# RFFI_pwrCtrl_Integrated_rev02_2021-05-18.net
KiCad netlist of a schematic drawn in EasyEDA
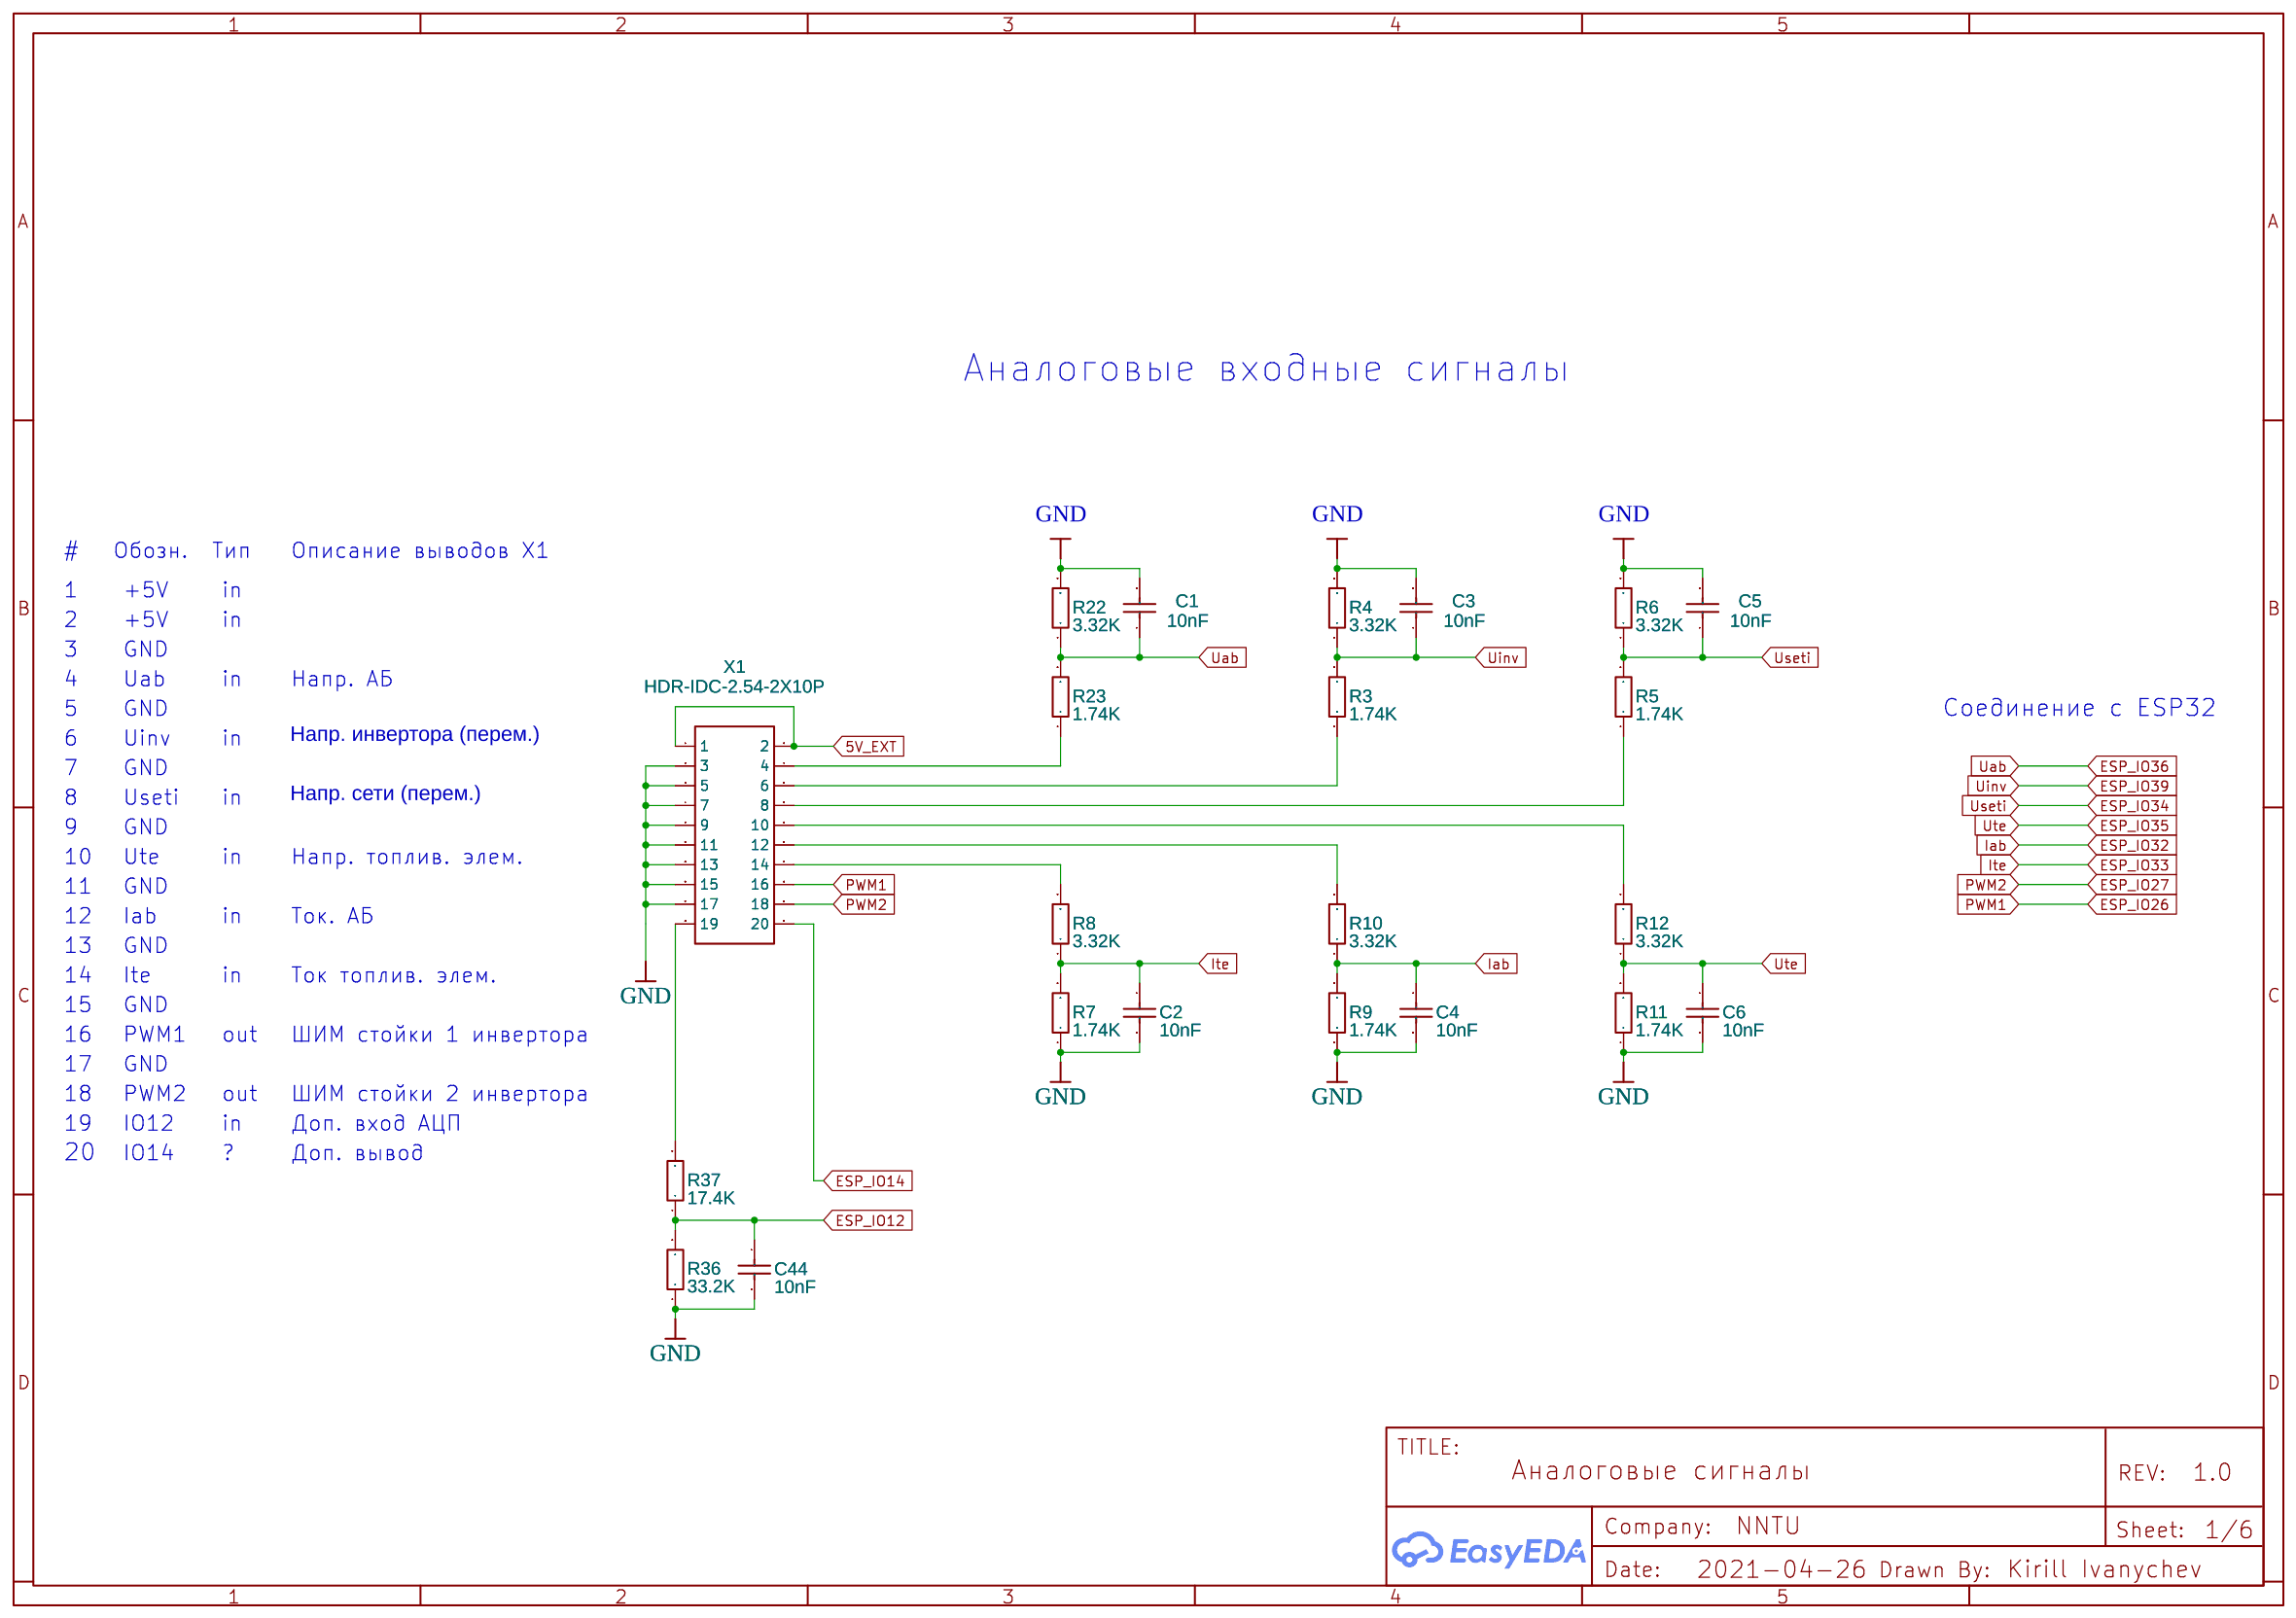
[diagram p0: Analog Signals]
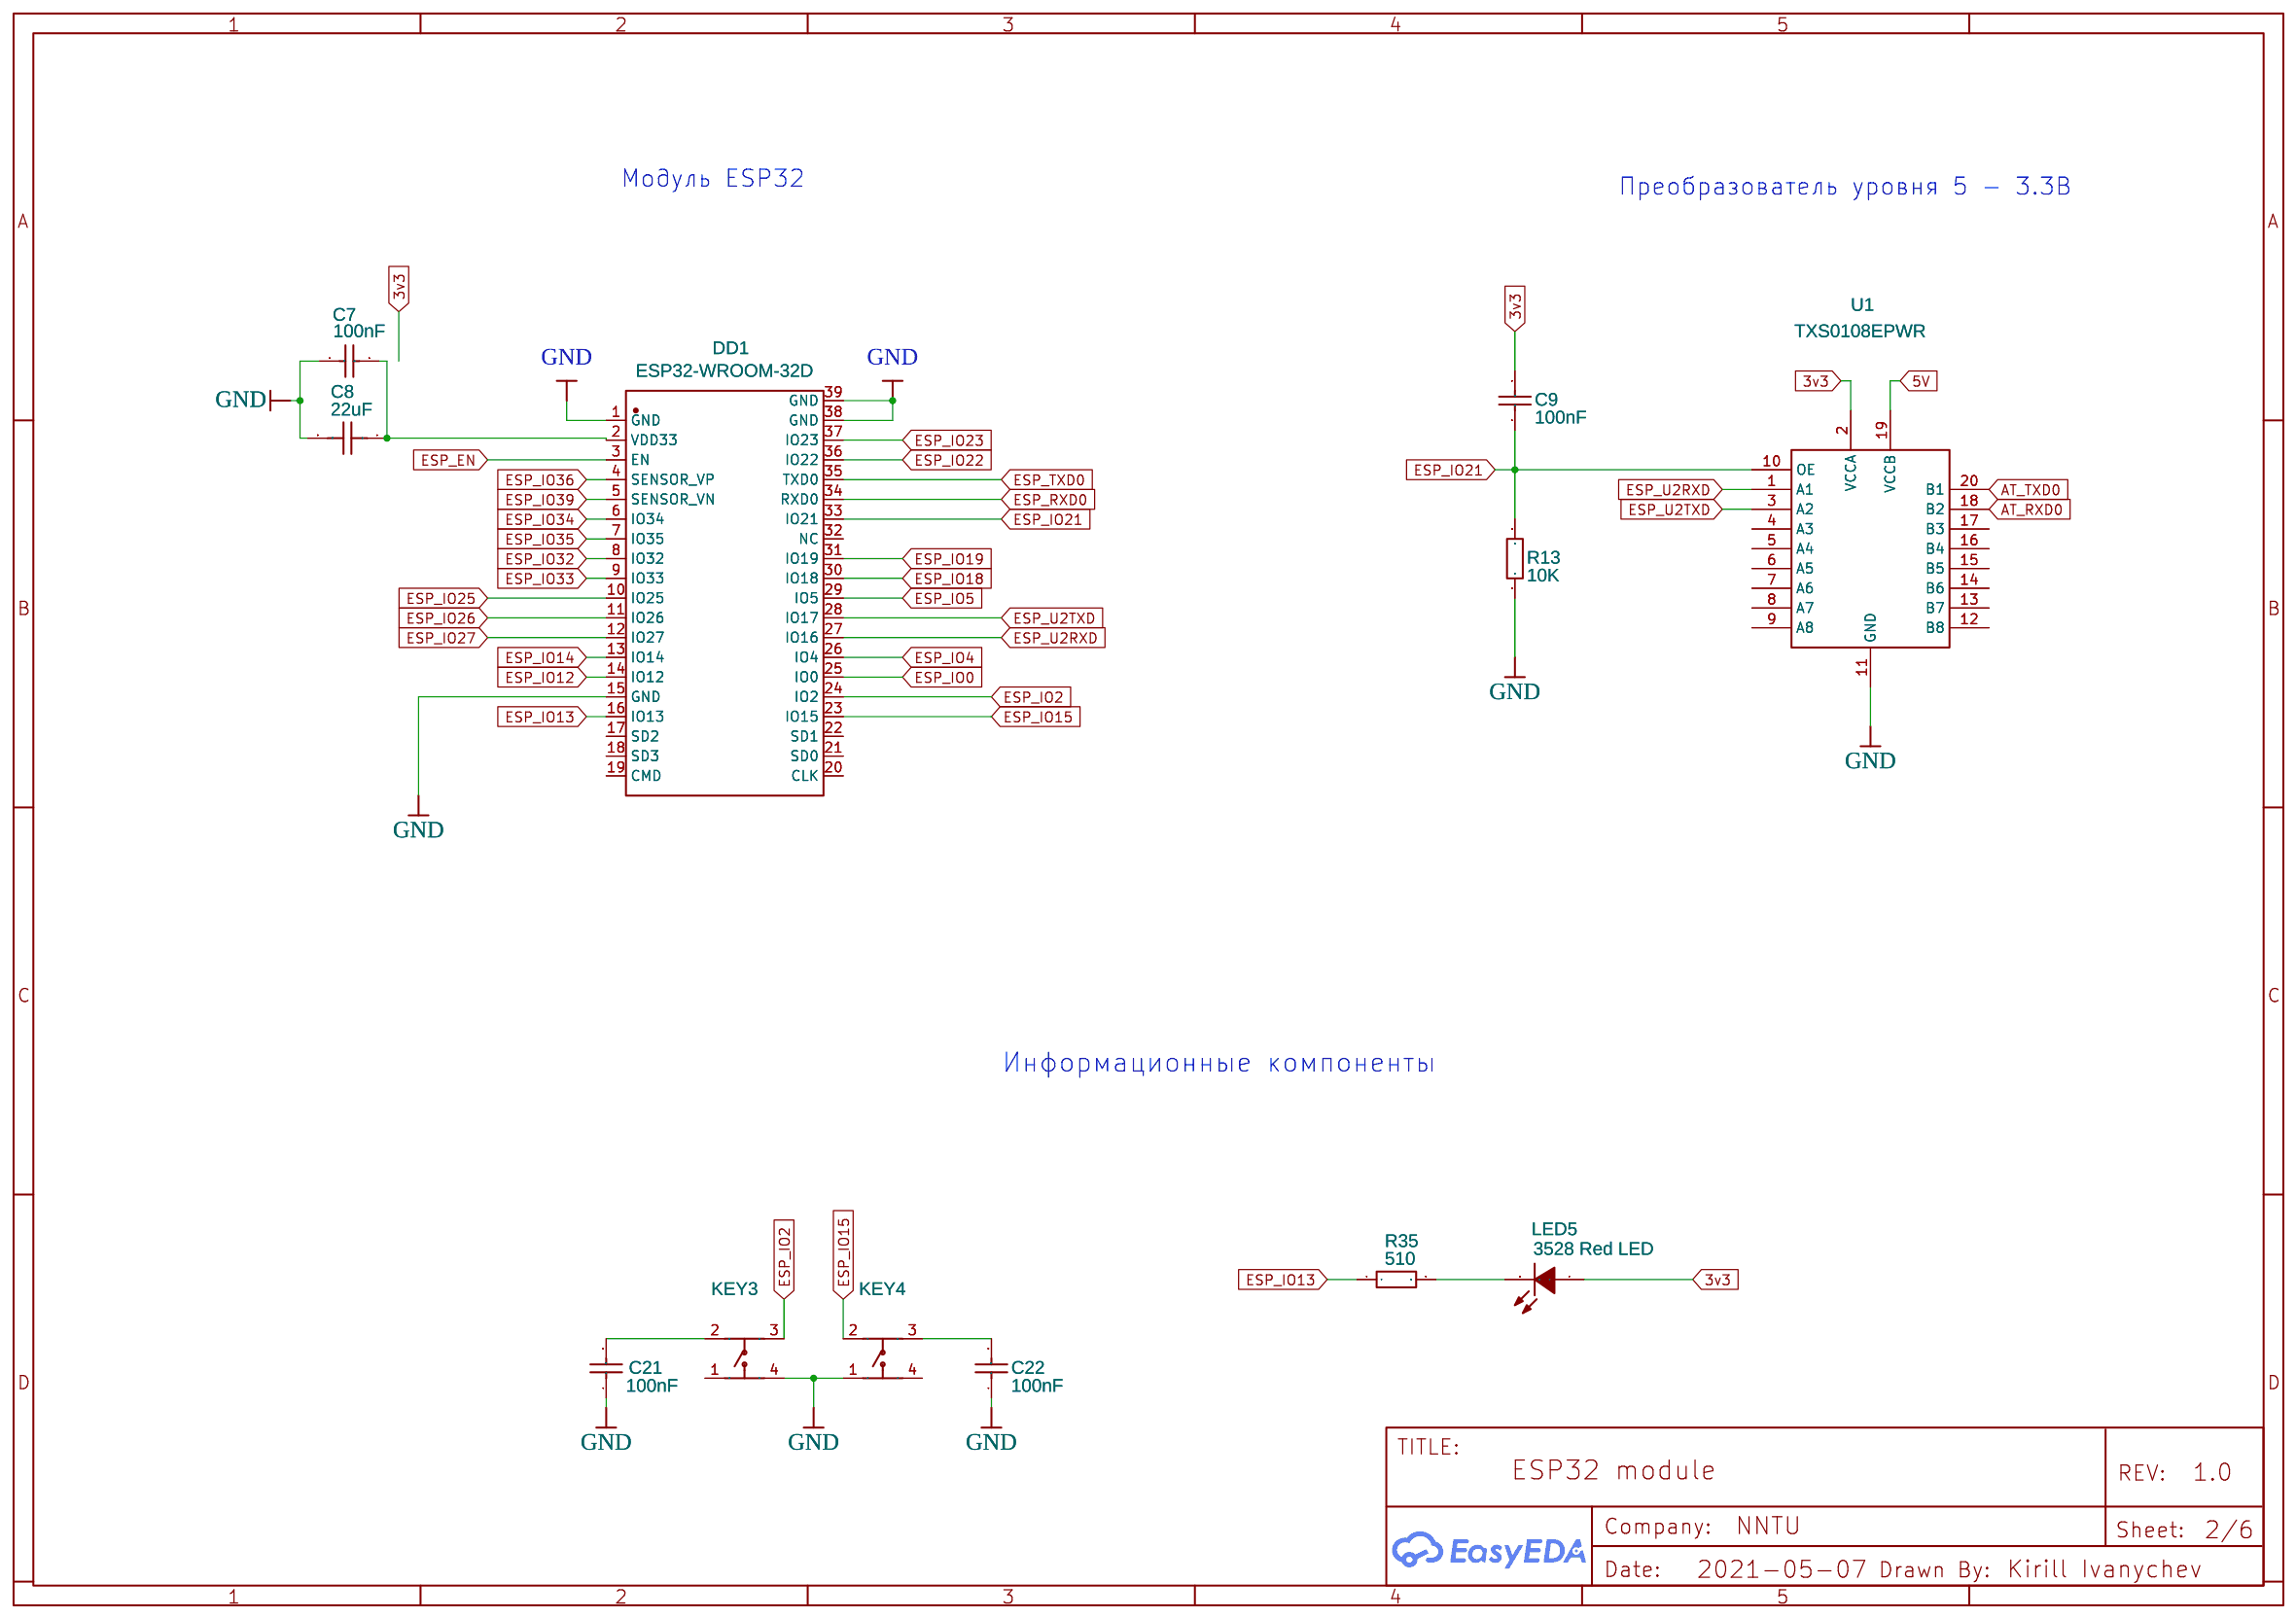
[diagram p1: ESP32 module]
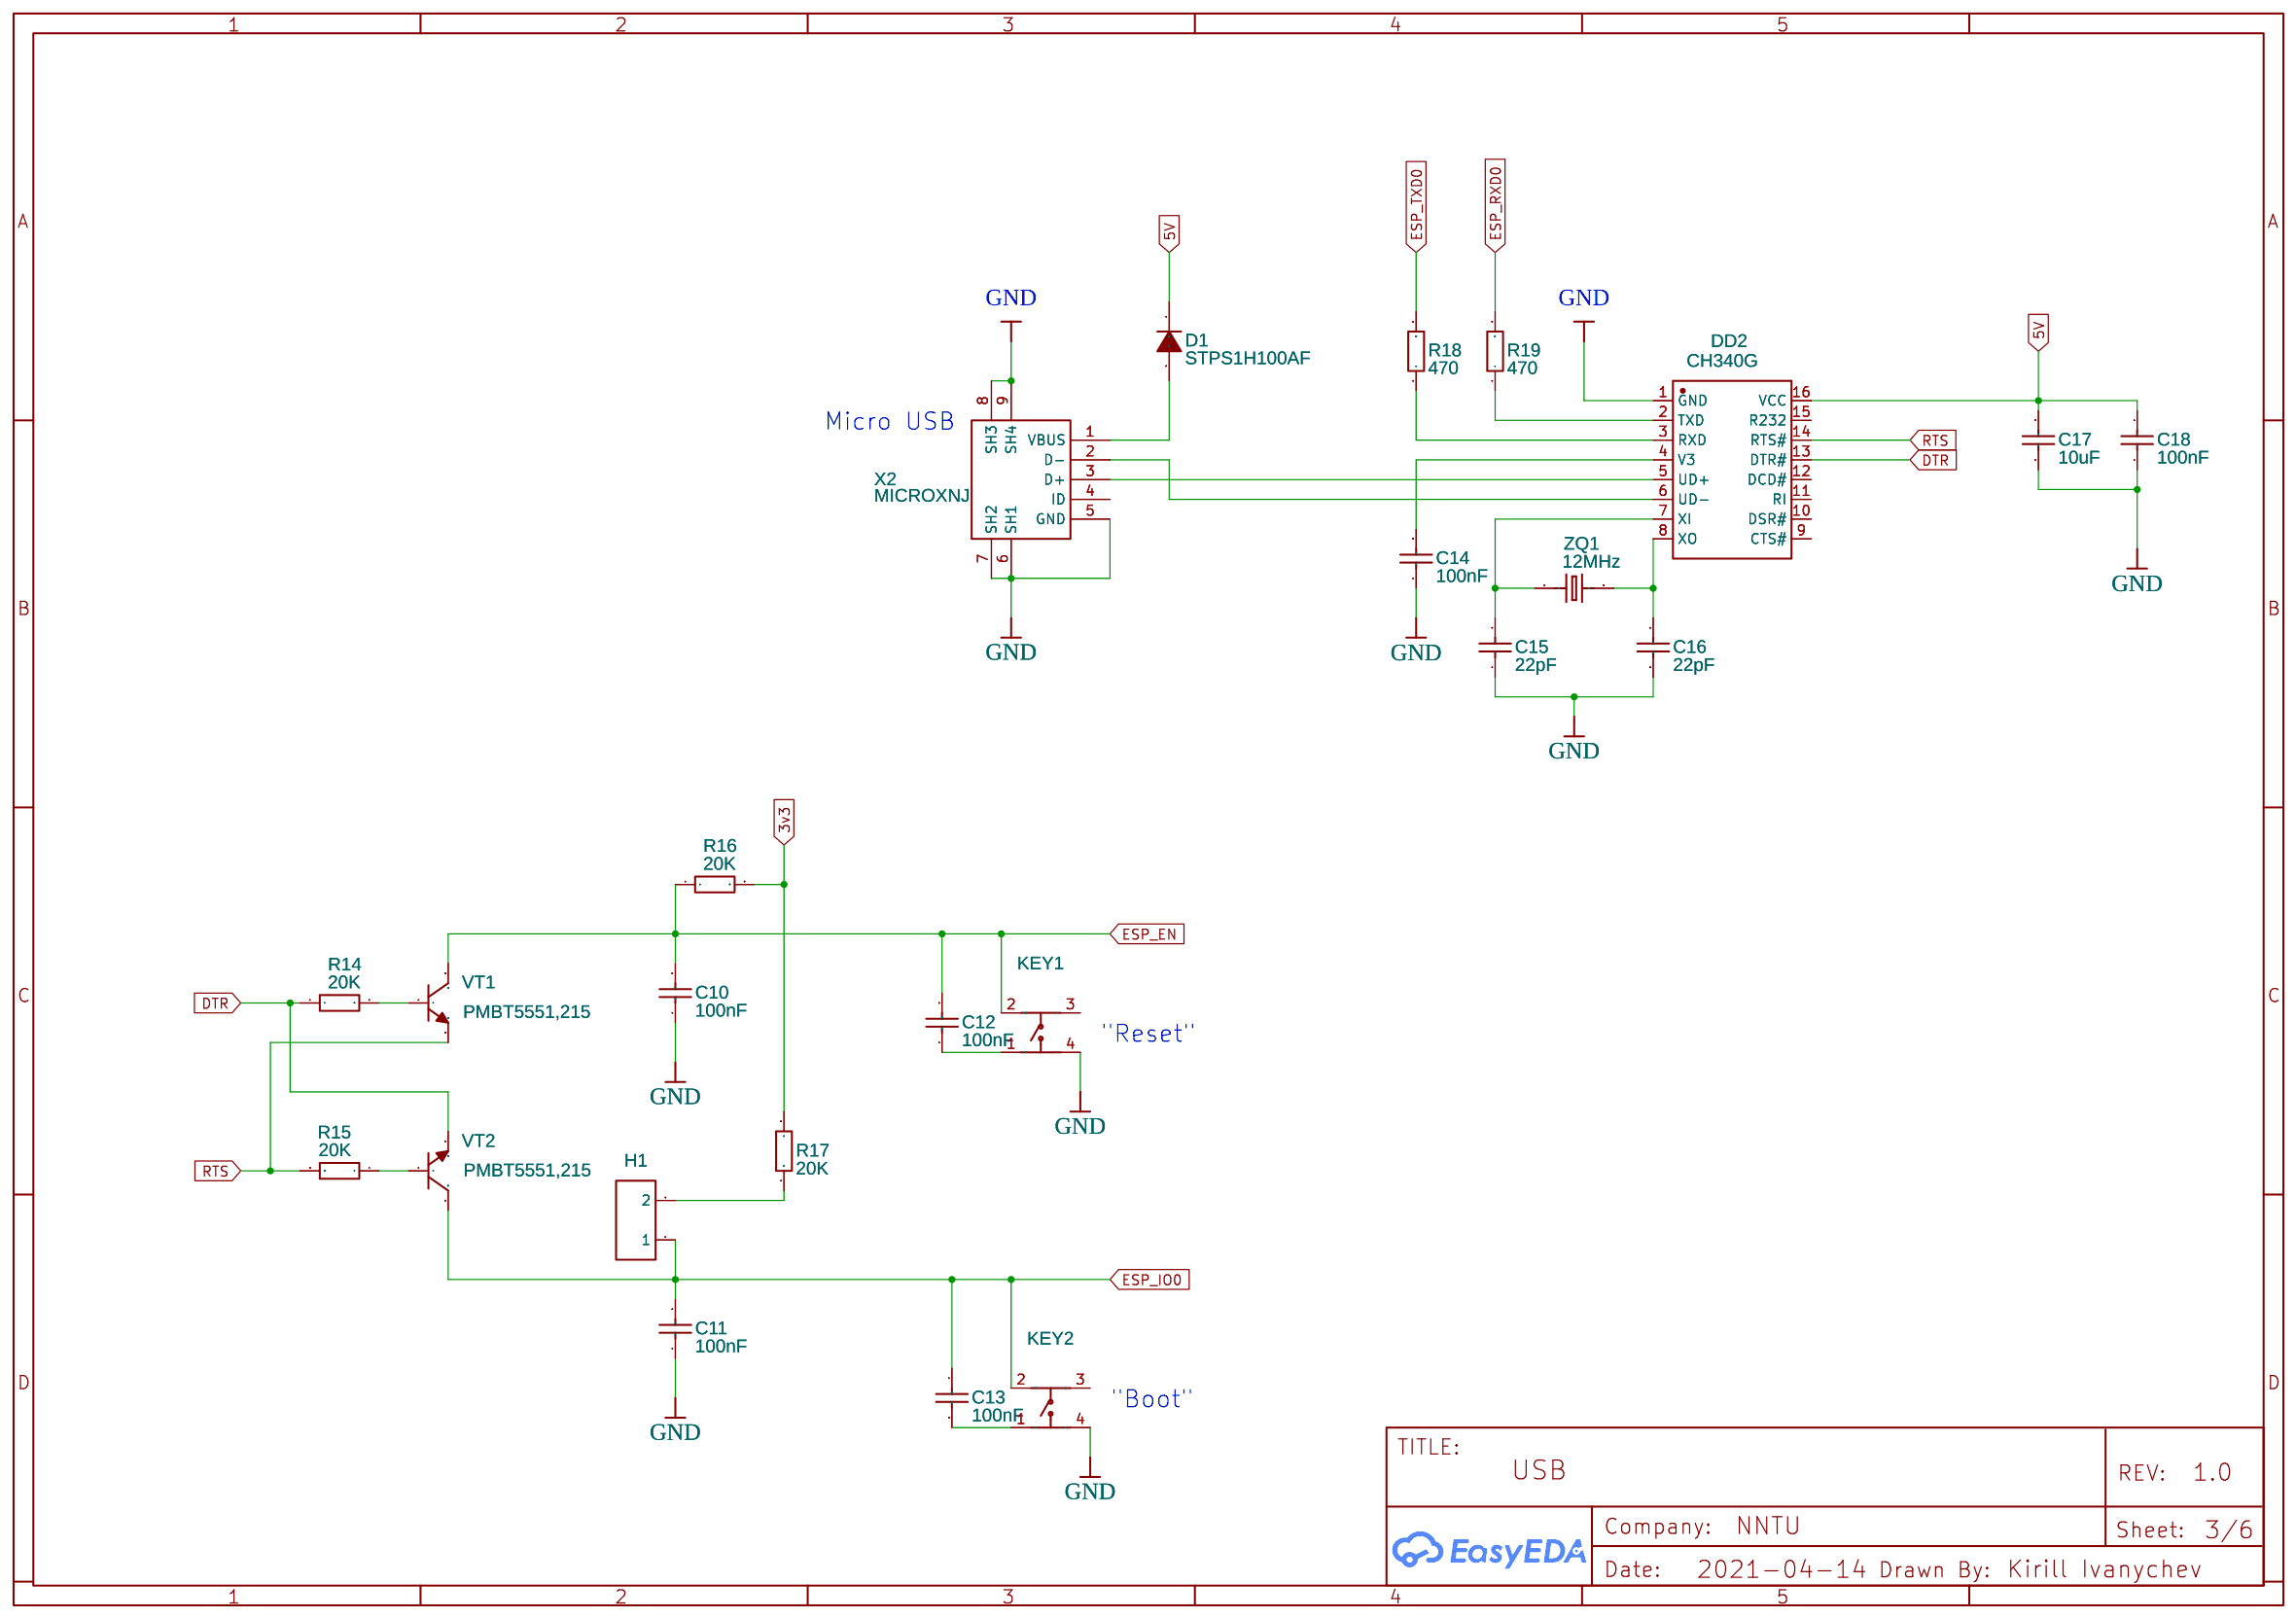
[diagram p2: USB]
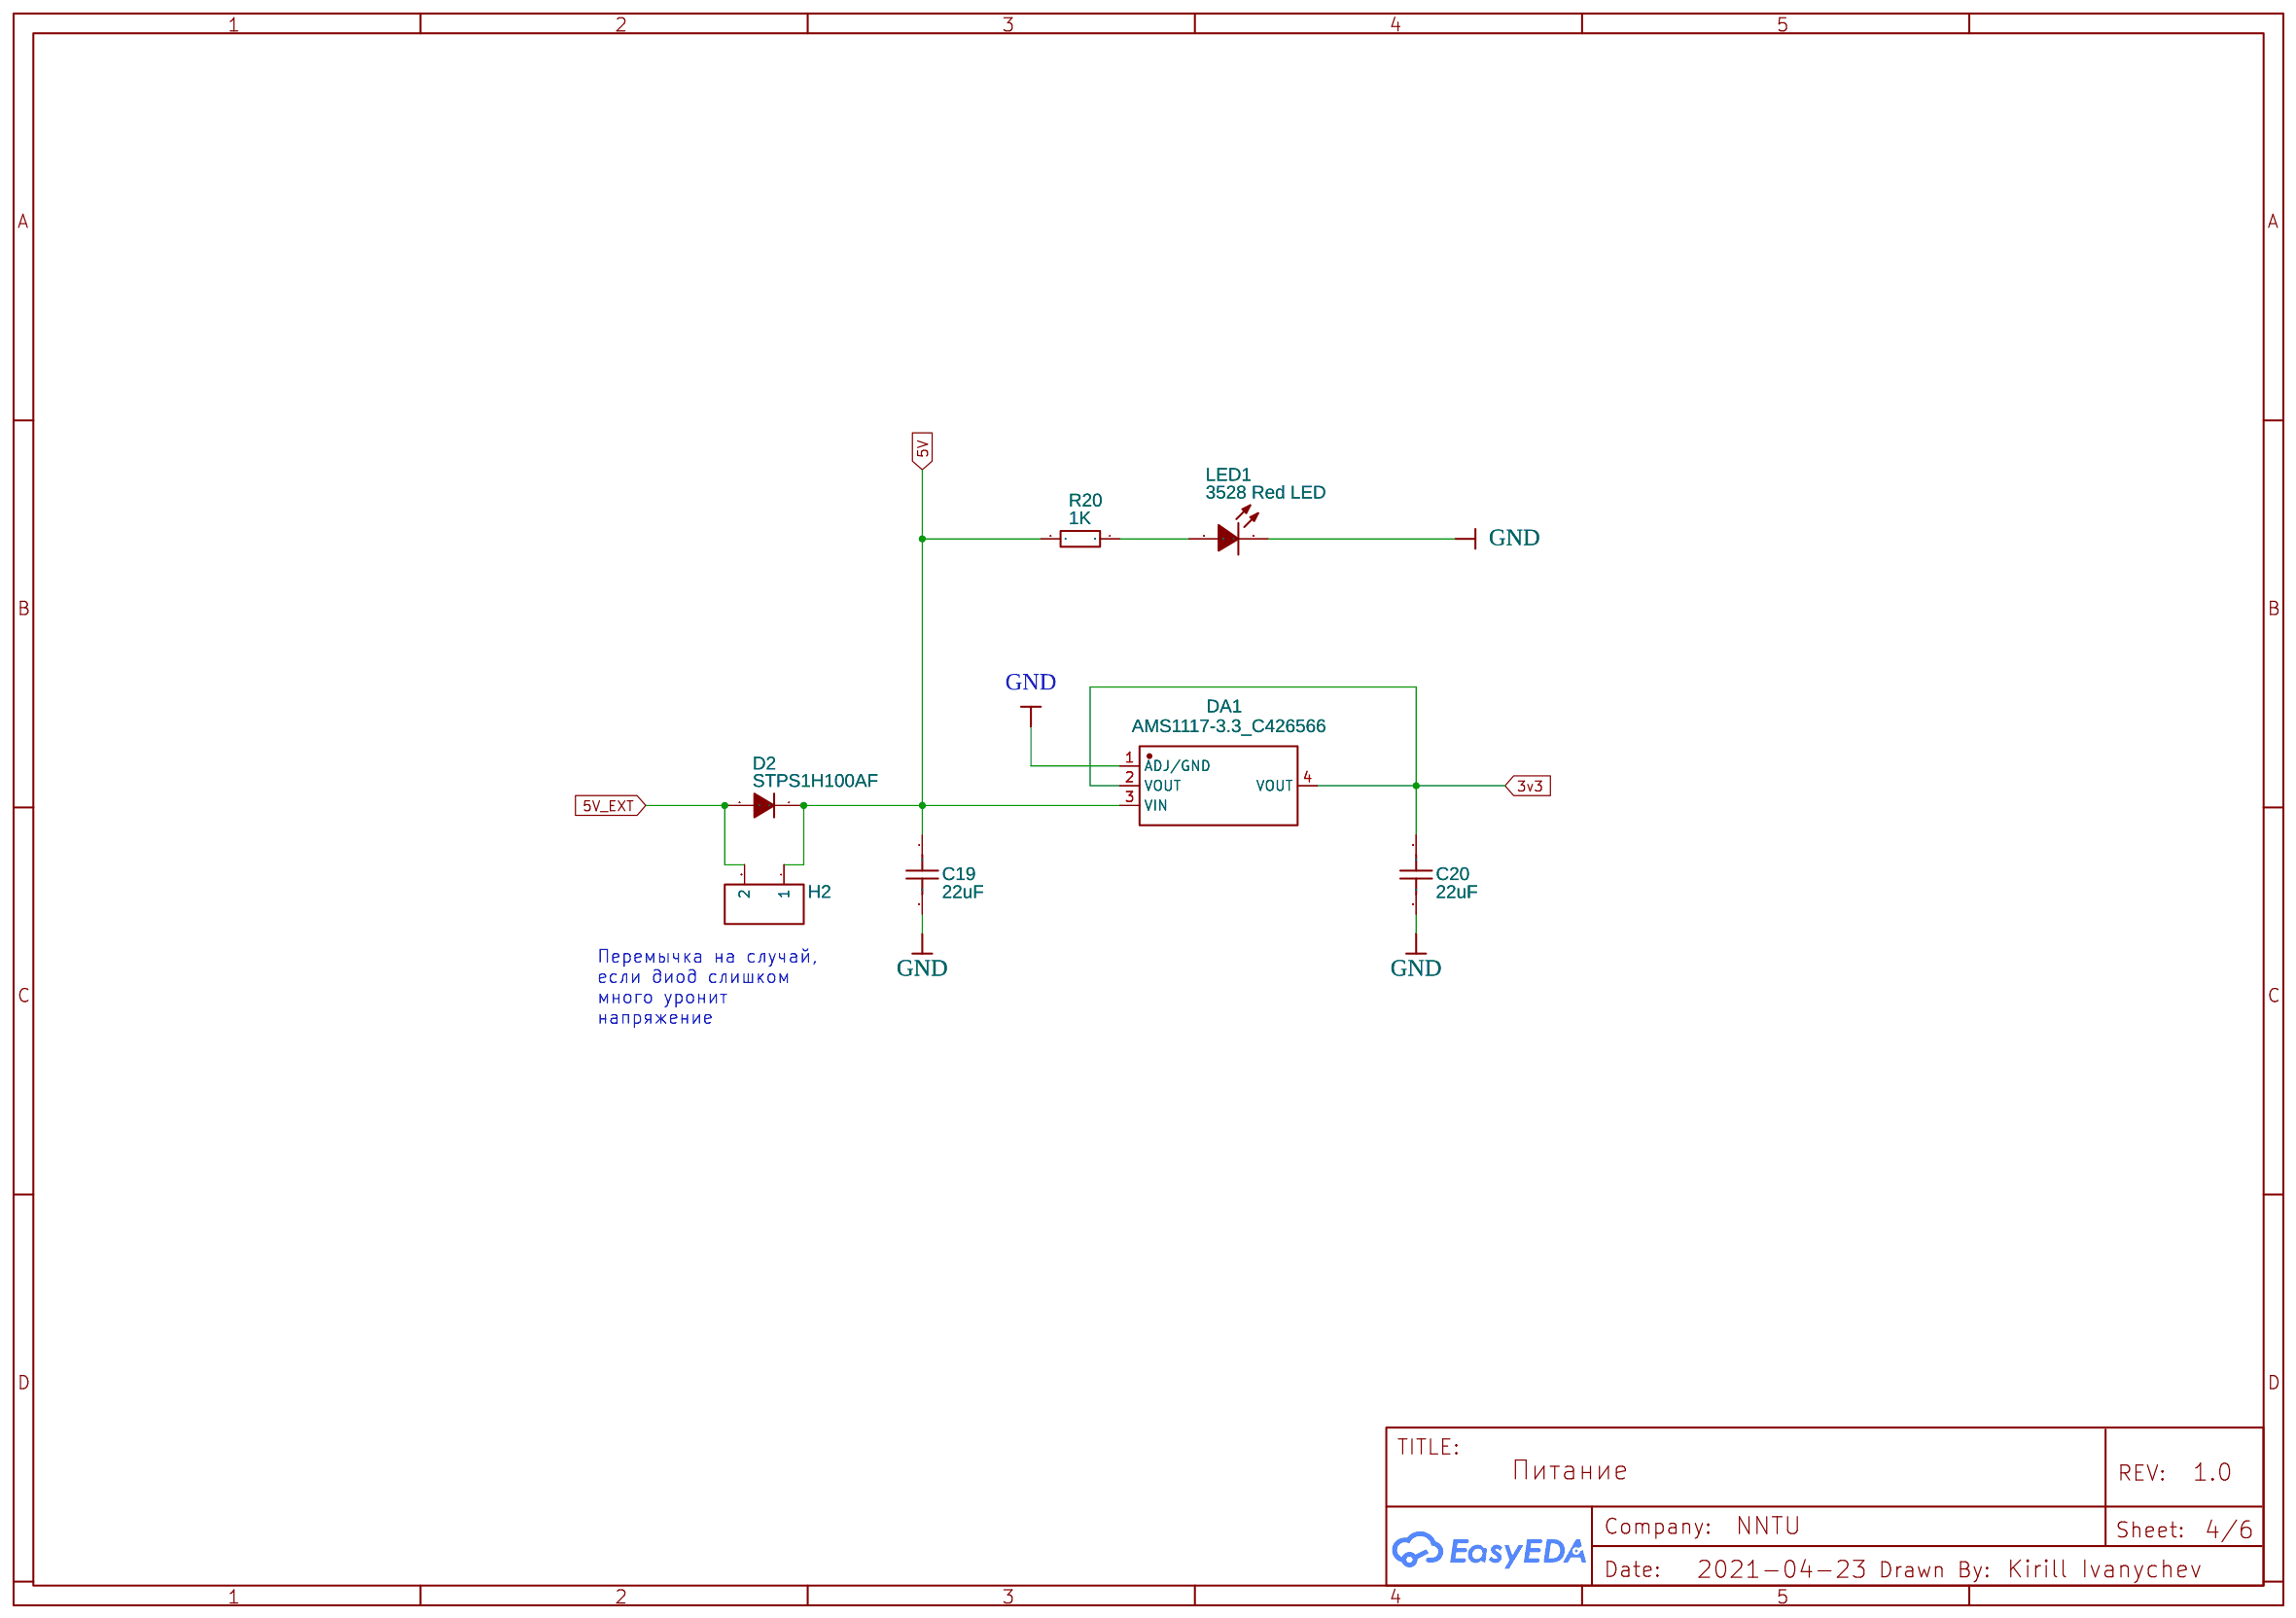
[diagram p3: Power]
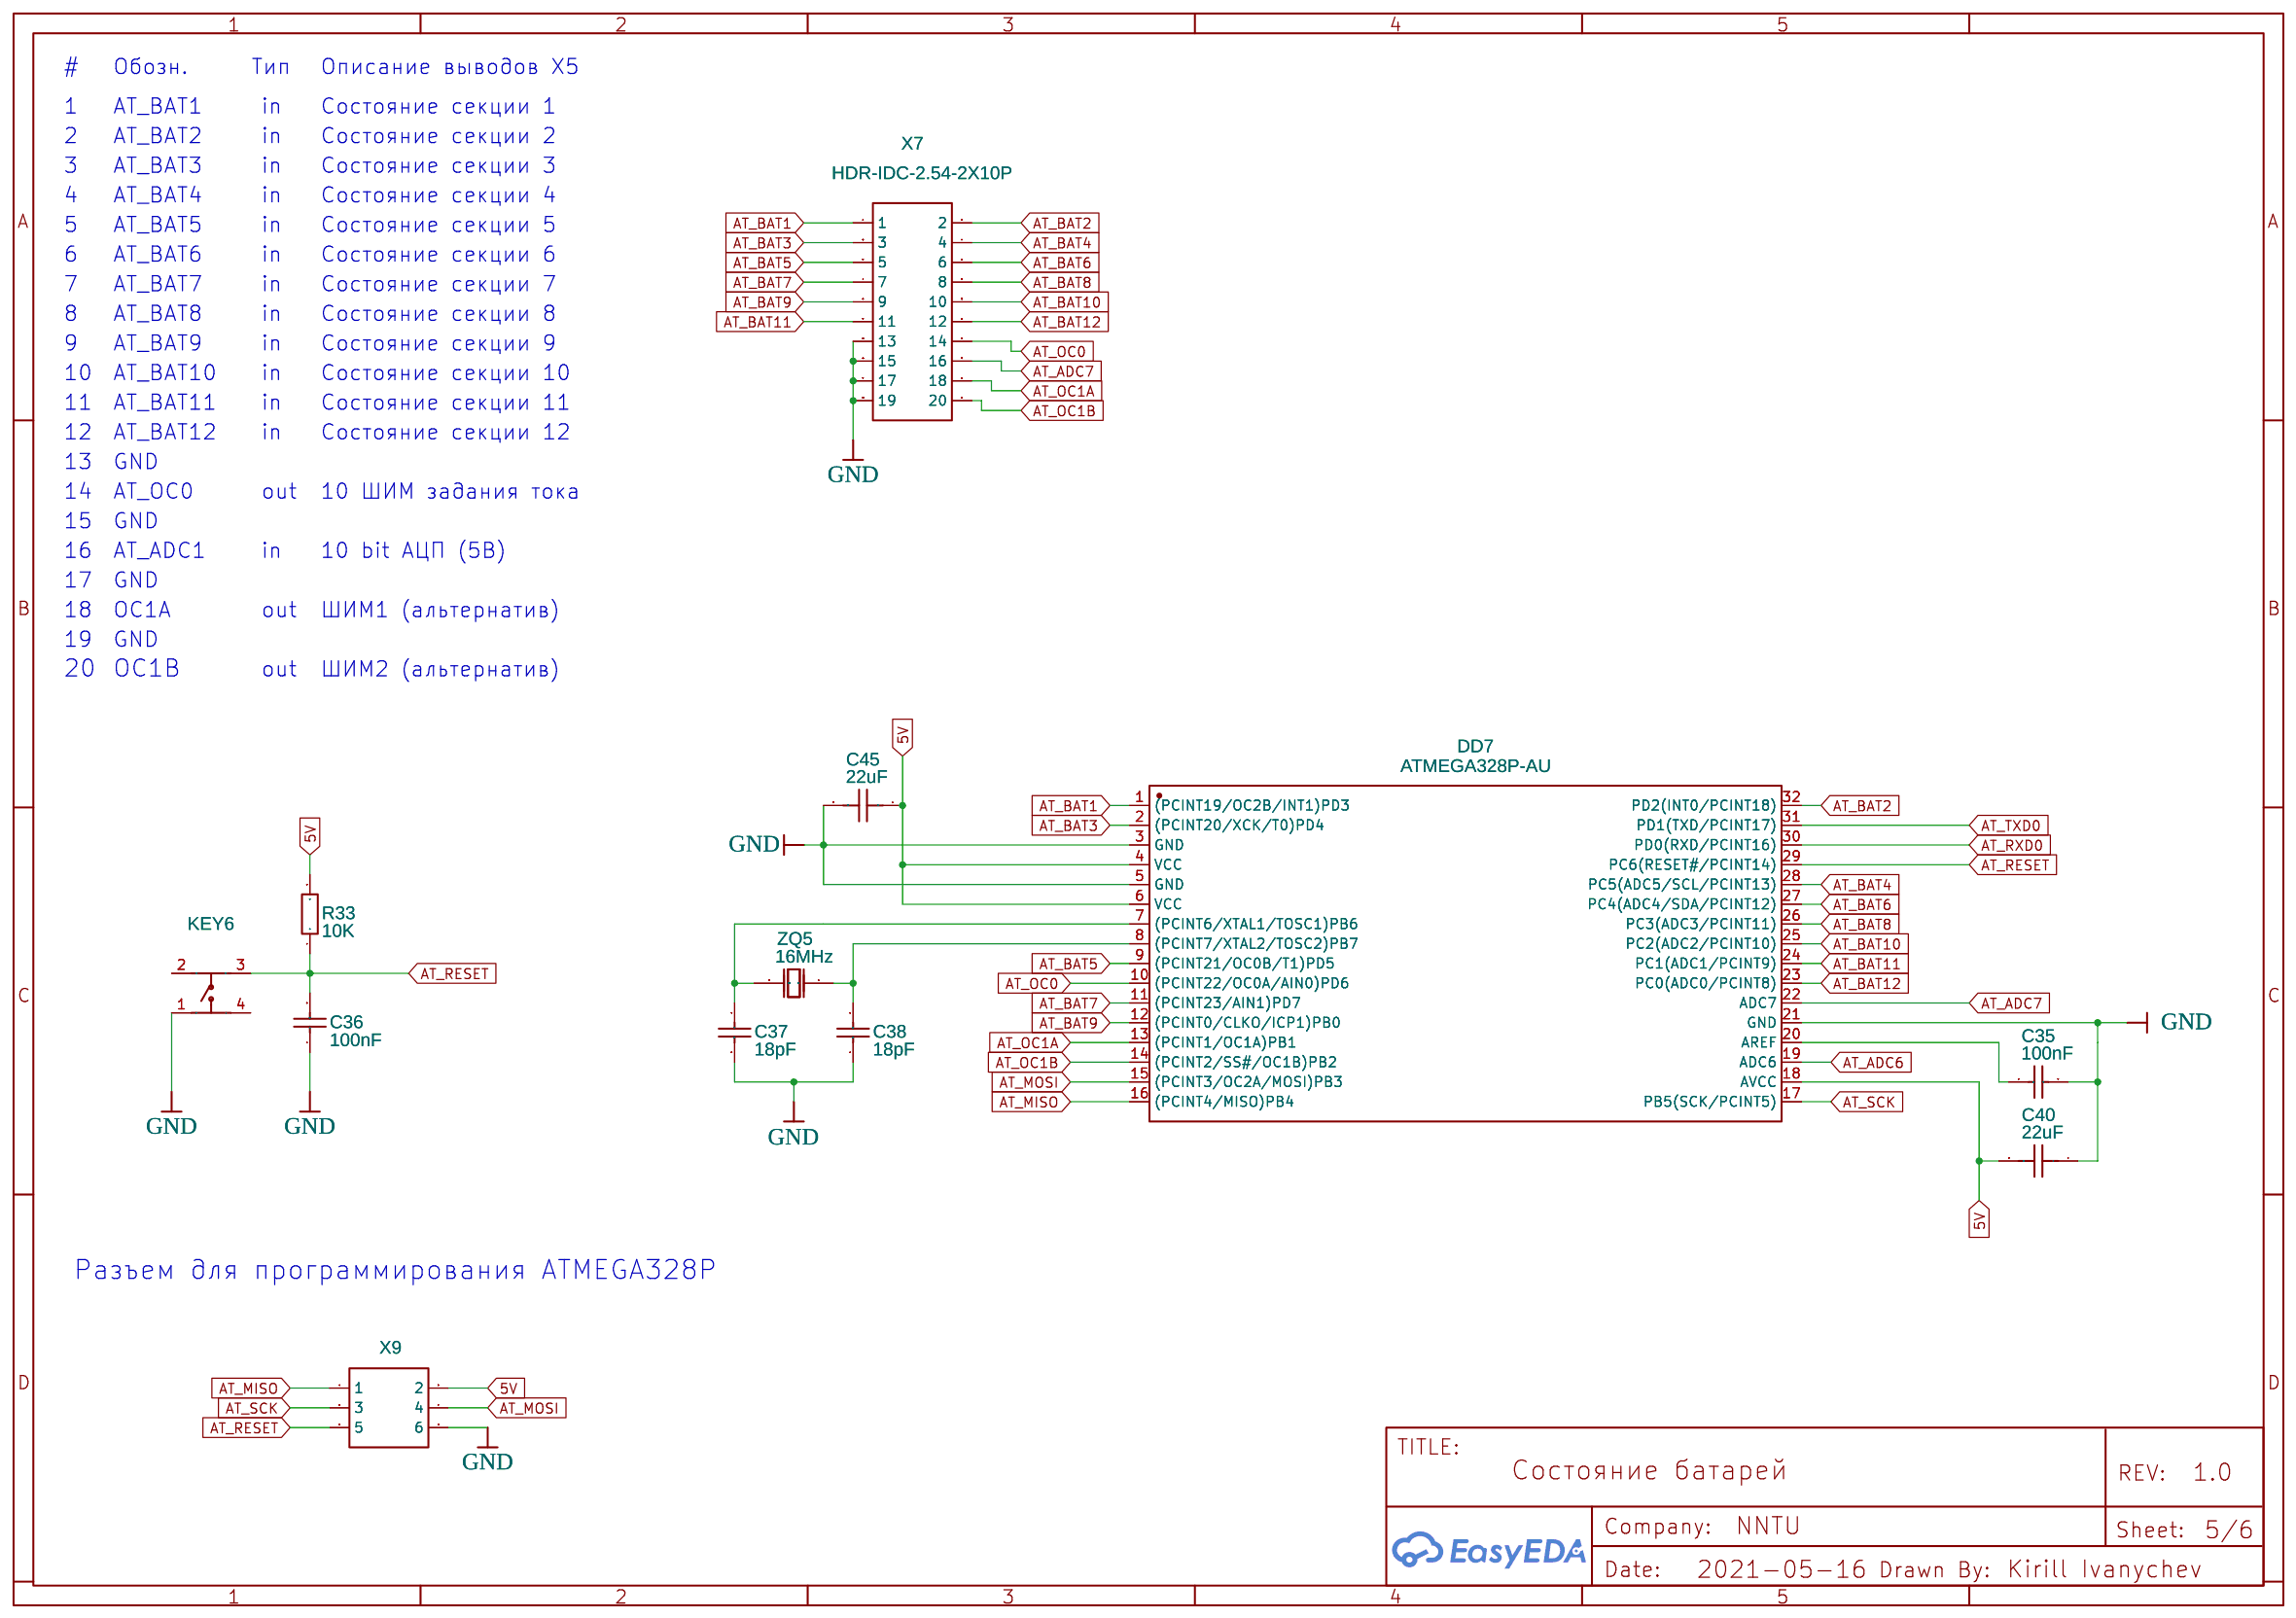
[diagram p4: Batteries]
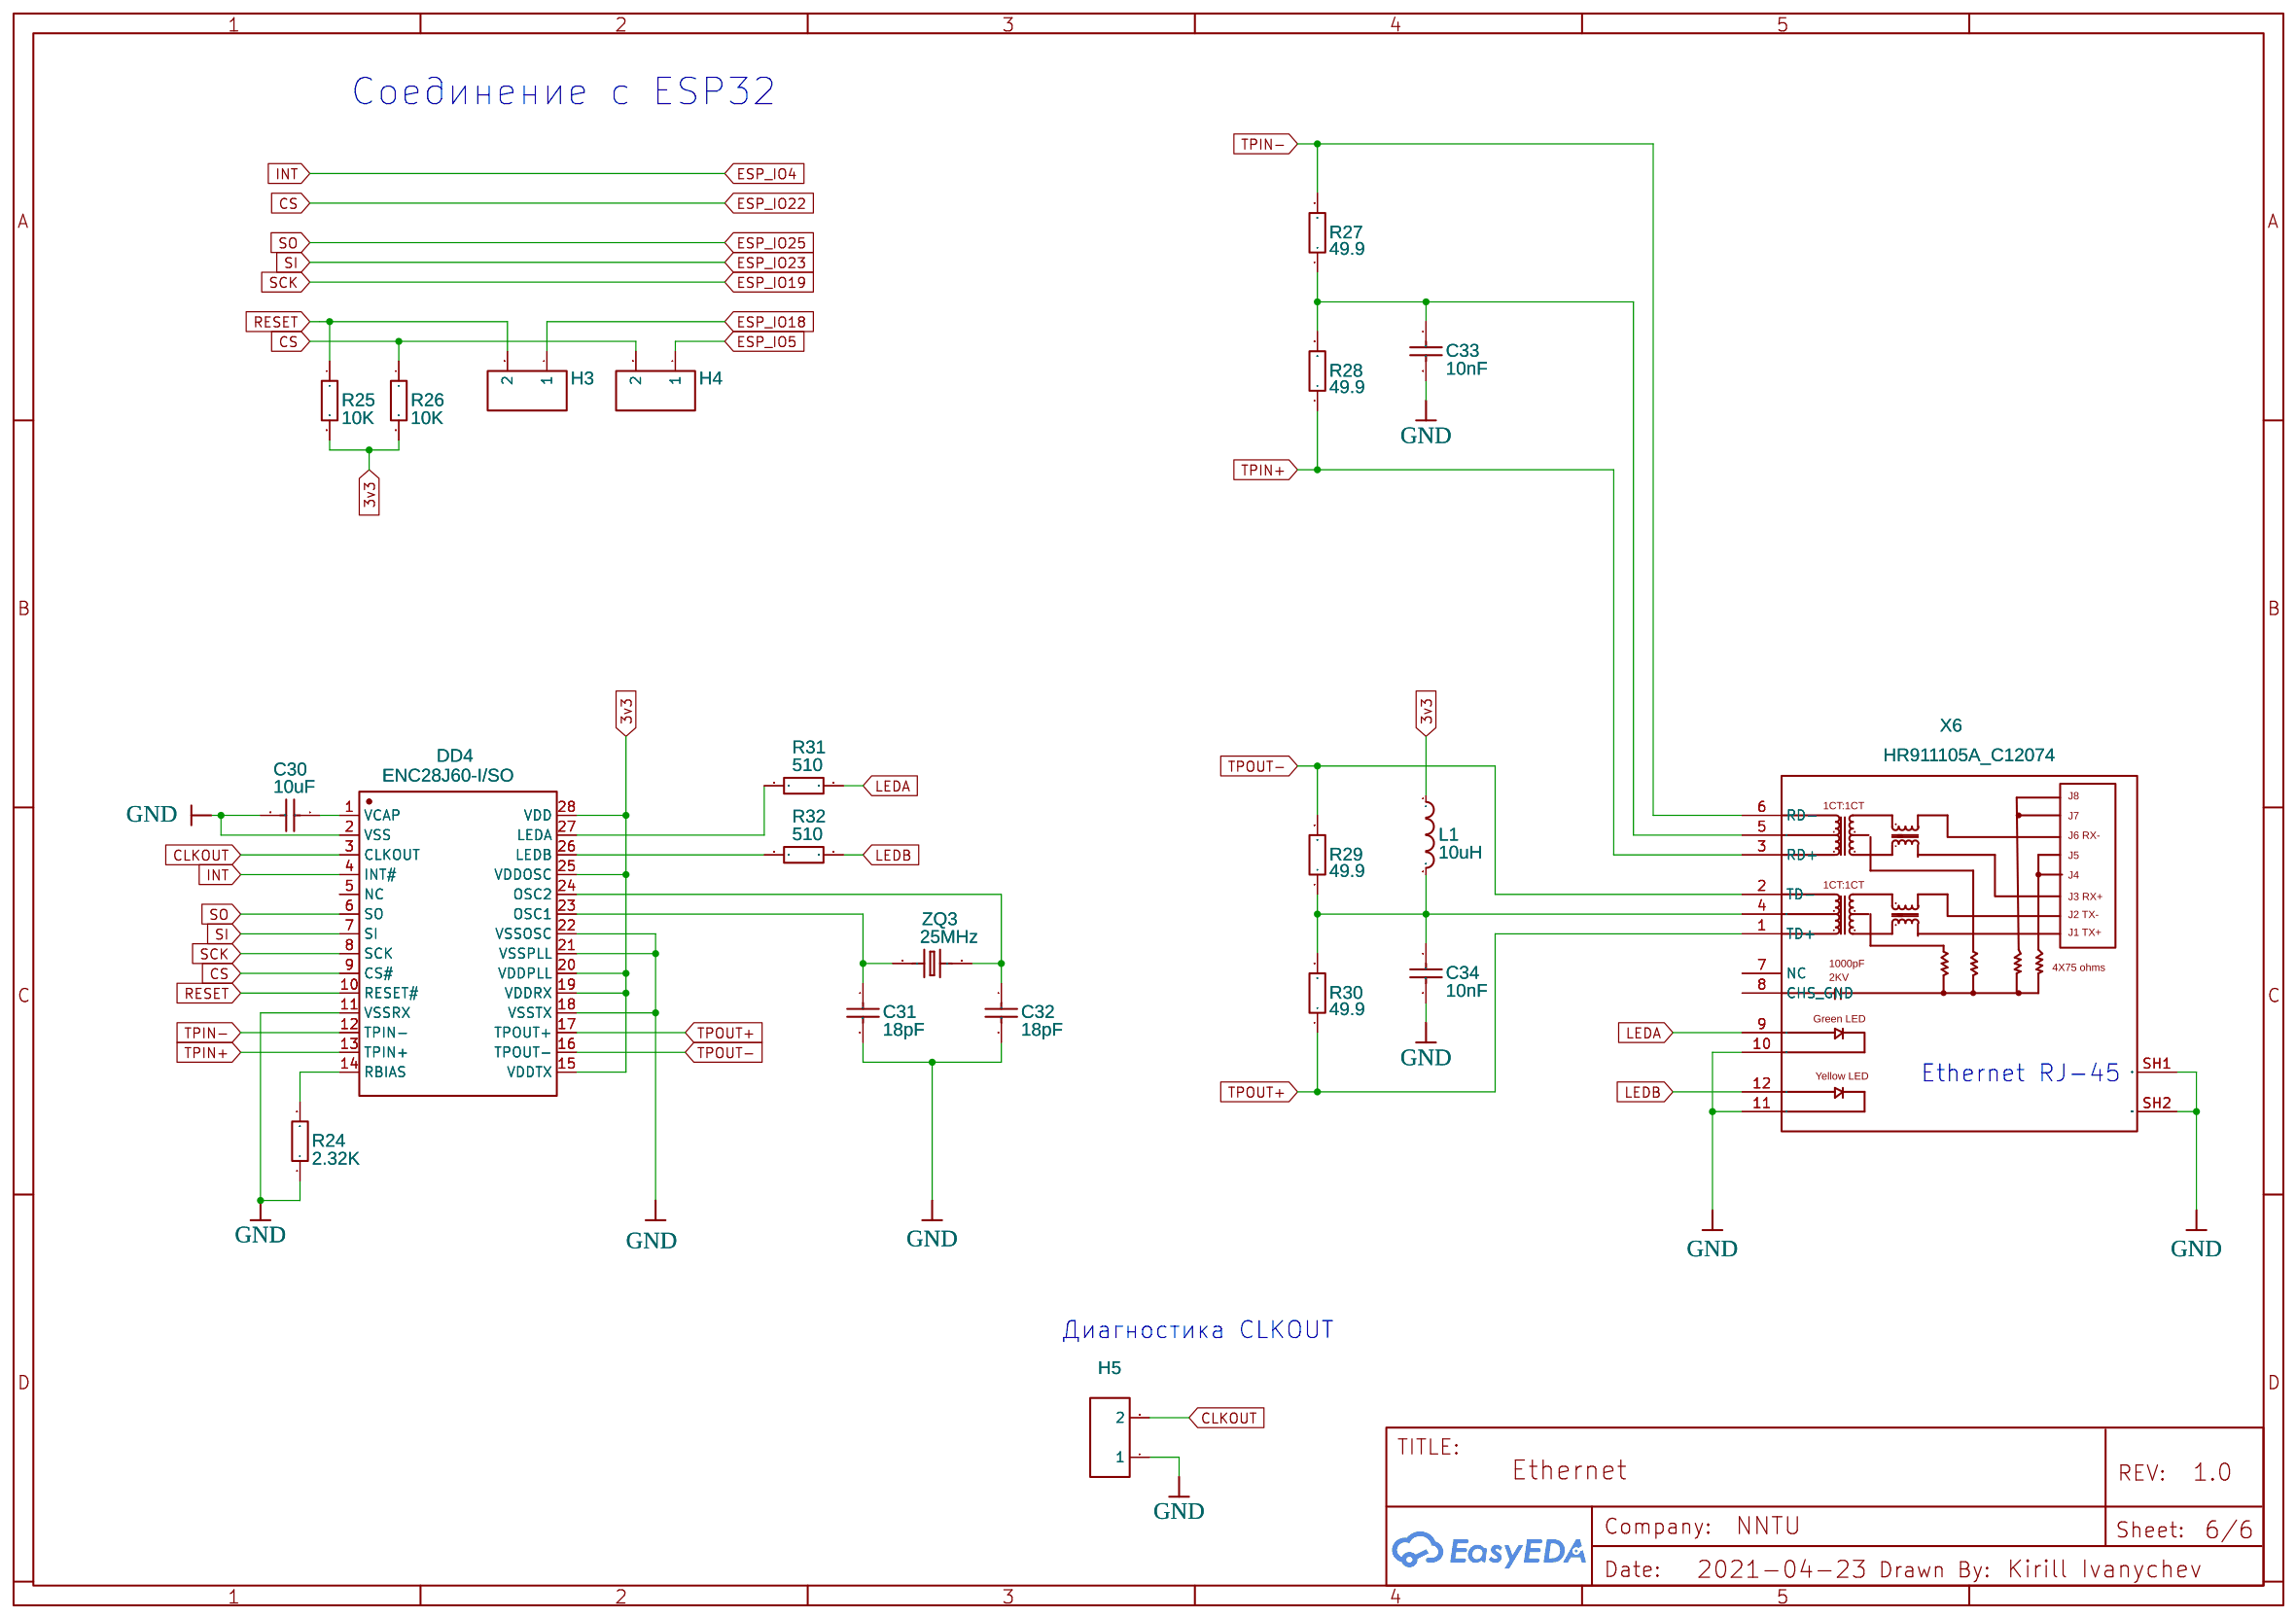
[diagram p5: Ethernet]

(export (version "E")
  (design (tool "Eeschema 10.0.6"))
  (components
    (comp (ref "C1")
      (value "10nF")
      (fields
        (field (name "BOM_Manufacturer Part") "1206B103K500NT")
        (field (name "BOM_Supplier Part") "C1846")
      )
      (libsource (lib "") (part "1206B103K500NT_1"))
    )
    (comp (ref "C2")
      (value "10nF")
      (fields
        (field (name "BOM_Manufacturer Part") "1206B103K500NT")
        (field (name "BOM_Supplier Part") "C1846")
      )
      (libsource (lib "") (part "1206B103K500NT"))
    )
    (comp (ref "C3")
      (value "10nF")
      (fields
        (field (name "BOM_Manufacturer Part") "1206B103K500NT")
        (field (name "BOM_Supplier Part") "C1846")
      )
      (libsource (lib "") (part "1206B103K500NT_1"))
    )
    (comp (ref "C4")
      (value "10nF")
      (fields
        (field (name "BOM_Manufacturer Part") "1206B103K500NT")
        (field (name "BOM_Supplier Part") "C1846")
      )
      (libsource (lib "") (part "1206B103K500NT"))
    )
    (comp (ref "C5")
      (value "10nF")
      (fields
        (field (name "BOM_Manufacturer Part") "1206B103K500NT")
        (field (name "BOM_Supplier Part") "C1846")
      )
      (libsource (lib "") (part "1206B103K500NT_1"))
    )
    (comp (ref "C6")
      (value "10nF")
      (fields
        (field (name "BOM_Manufacturer Part") "1206B103K500NT")
        (field (name "BOM_Supplier Part") "C1846")
      )
      (libsource (lib "") (part "1206B103K500NT"))
    )
    (comp (ref "C44")
      (value "10nF")
      (fields
        (field (name "BOM_Manufacturer Part") "1206B103K500NT")
        (field (name "BOM_Supplier Part") "C1846")
      )
      (libsource (lib "") (part "1206B103K500NT"))
    )
    (comp (ref "R3")
      (value "1.74K")
      (fields
        (field (name "BOM_Manufacturer Part") "0402WGF1741TCE")
        (field (name "BOM_Supplier Part") "C270638")
      )
      (libsource (lib "") (part "0402WGF1741TCE"))
    )
    (comp (ref "R4")
      (value "3.32K")
      (fields
        (field (name "BOM_Manufacturer Part") "0603WAF3321T5E")
        (field (name "BOM_Supplier Part") "C22995")
      )
      (libsource (lib "") (part "0603WAF3321T5E"))
    )
    (comp (ref "R5")
      (value "1.74K")
      (fields
        (field (name "BOM_Manufacturer Part") "0402WGF1741TCE")
        (field (name "BOM_Supplier Part") "C270638")
      )
      (libsource (lib "") (part "0402WGF1741TCE"))
    )
    (comp (ref "R6")
      (value "3.32K")
      (fields
        (field (name "BOM_Manufacturer Part") "0603WAF3321T5E")
        (field (name "BOM_Supplier Part") "C22995")
      )
      (libsource (lib "") (part "0603WAF3321T5E"))
    )
    (comp (ref "R7")
      (value "1.74K")
      (fields
        (field (name "BOM_Manufacturer Part") "0402WGF1741TCE")
        (field (name "BOM_Supplier Part") "C270638")
      )
      (libsource (lib "") (part "0402WGF1741TCE"))
    )
    (comp (ref "R8")
      (value "3.32K")
      (fields
        (field (name "BOM_Manufacturer Part") "0603WAF3321T5E")
        (field (name "BOM_Supplier Part") "C22995")
      )
      (libsource (lib "") (part "0603WAF3321T5E"))
    )
    (comp (ref "R9")
      (value "1.74K")
      (fields
        (field (name "BOM_Manufacturer Part") "0402WGF1741TCE")
        (field (name "BOM_Supplier Part") "C270638")
      )
      (libsource (lib "") (part "0402WGF1741TCE"))
    )
    (comp (ref "R10")
      (value "3.32K")
      (fields
        (field (name "BOM_Manufacturer Part") "0603WAF3321T5E")
        (field (name "BOM_Supplier Part") "C22995")
      )
      (libsource (lib "") (part "0603WAF3321T5E"))
    )
    (comp (ref "R11")
      (value "1.74K")
      (fields
        (field (name "BOM_Manufacturer Part") "0402WGF1741TCE")
        (field (name "BOM_Supplier Part") "C270638")
      )
      (libsource (lib "") (part "0402WGF1741TCE"))
    )
    (comp (ref "R12")
      (value "3.32K")
      (fields
        (field (name "BOM_Manufacturer Part") "0603WAF3321T5E")
        (field (name "BOM_Supplier Part") "C22995")
      )
      (libsource (lib "") (part "0603WAF3321T5E"))
    )
    (comp (ref "R22")
      (value "3.32K")
      (fields
        (field (name "BOM_Manufacturer Part") "0603WAF3321T5E")
        (field (name "BOM_Supplier Part") "C22995")
      )
      (libsource (lib "") (part "0603WAF3321T5E"))
    )
    (comp (ref "R23")
      (value "1.74K")
      (fields
        (field (name "BOM_Manufacturer Part") "0402WGF1741TCE")
        (field (name "BOM_Supplier Part") "C270638")
      )
      (libsource (lib "") (part "0402WGF1741TCE"))
    )
    (comp (ref "R36")
      (value "33.2K")
      (fields
        (field (name "BOM_Manufacturer Part") "0603WAF3322T5E")
        (field (name "BOM_Supplier Part") "C23003")
      )
      (libsource (lib "") (part "0603WAF3322T5E"))
    )
    (comp (ref "R37")
      (value "17.4K")
      (fields
        (field (name "BOM_Manufacturer Part") "0402WGF1742TCE")
        (field (name "BOM_Supplier Part") "C26957")
      )
      (libsource (lib "") (part "0402WGF1742TCE"))
    )
    (comp (ref "X1")
      (value "HDR-IDC-2.54-2X10P")
      (fields
        (field (name "BOM_Manufacturer Part") "IDC Box 2.54mm 2X10P　Straight")
        (field (name "BOM_Supplier Part") "C3405")
      )
      (libsource (lib "") (part "HDR-IDC-2.54-2X10P"))
    )
    (comp (ref "C7")
      (value "100nF")
      (fields
        (field (name "BOM_Manufacturer Part") "CL21B104JBCNNNC")
        (field (name "BOM_Supplier Part") "C62912")
      )
      (libsource (lib "") (part "CL21B104JBCNNNC"))
    )
    (comp (ref "C8")
      (value "22uF")
      (fields
        (field (name "BOM_Manufacturer Part") "CL21A226MQQNNNE")
        (field (name "BOM_Supplier Part") "C5674")
      )
      (libsource (lib "") (part "CL21A226MQQNNNE"))
    )
    (comp (ref "C9")
      (value "100nF")
      (fields
        (field (name "BOM_Manufacturer Part") "CL21B104JBCNNNC")
        (field (name "BOM_Supplier Part") "C62912")
      )
      (libsource (lib "") (part "CL21B104JBCNNNC_2"))
    )
    (comp (ref "C21")
      (value "100nF")
      (fields
        (field (name "BOM_Manufacturer Part") "CL21B104JBCNNNC")
        (field (name "BOM_Supplier Part") "C62912")
      )
      (libsource (lib "") (part "CL21B104JBCNNNC_1"))
    )
    (comp (ref "C22")
      (value "100nF")
      (fields
        (field (name "BOM_Manufacturer Part") "CL21B104JBCNNNC")
        (field (name "BOM_Supplier Part") "C62912")
      )
      (libsource (lib "") (part "CL21B104JBCNNNC_1"))
    )
    (comp (ref "DD1")
      (value "ESP32-WROOM-32D")
      (fields (field (name "BOM_Supplier Part") "C473012"))
      (libsource (lib "") (part "ESP32-WROOM-32D"))
    )
    (comp (ref "KEY3")
      (value "TSA063G50-250")
      (fields (field (name "BOM_Supplier Part") "C294565"))
      (libsource (lib "") (part "TSA063G50-250"))
    )
    (comp (ref "KEY4")
      (value "TSA063G50-250")
      (fields (field (name "BOM_Supplier Part") "C294565"))
      (libsource (lib "") (part "TSA063G50-250"))
    )
    (comp (ref "LED5")
      (value "3528 Red LED")
      (fields (field (name "BOM_Supplier Part") "C2305"))
      (libsource (lib "") (part "3528 Red LED"))
    )
    (comp (ref "R13")
      (value "10K")
      (fields
        (field (name "BOM_Manufacturer Part") "ARG03FTC1002")
        (field (name "BOM_Supplier Part") "C217687")
      )
      (libsource (lib "") (part "ARG03FTC1002"))
    )
    (comp (ref "R35")
      (value "510")
      (fields
        (field (name "BOM_Manufacturer Part") "1206W4J0511T5E")
        (field (name "BOM_Supplier Part") "C25386")
      )
      (libsource (lib "") (part "1206W4J0511T5E"))
    )
    (comp (ref "U1")
      (value "TXS0108EPWR")
      (fields (field (name "BOM_Supplier Part") "C17206"))
      (libsource (lib "") (part "TXS0108EPWR"))
    )
    (comp (ref "C10")
      (value "100nF")
      (fields
        (field (name "BOM_Manufacturer Part") "CL21B104JBCNNNC")
        (field (name "BOM_Supplier Part") "C62912")
      )
      (libsource (lib "") (part "CL21B104JBCNNNC"))
    )
    (comp (ref "C11")
      (value "100nF")
      (fields
        (field (name "BOM_Manufacturer Part") "CL21B104JBCNNNC")
        (field (name "BOM_Supplier Part") "C62912")
      )
      (libsource (lib "") (part "CL21B104JBCNNNC"))
    )
    (comp (ref "C12")
      (value "100nF")
      (fields
        (field (name "BOM_Manufacturer Part") "CL21B104JBCNNNC")
        (field (name "BOM_Supplier Part") "C62912")
      )
      (libsource (lib "") (part "CL21B104JBCNNNC"))
    )
    (comp (ref "C13")
      (value "100nF")
      (fields
        (field (name "BOM_Manufacturer Part") "CL21B104JBCNNNC")
        (field (name "BOM_Supplier Part") "C62912")
      )
      (libsource (lib "") (part "CL21B104JBCNNNC"))
    )
    (comp (ref "C14")
      (value "100nF")
      (fields
        (field (name "BOM_Manufacturer Part") "CL21B104JBCNNNC")
        (field (name "BOM_Supplier Part") "C62912")
      )
      (libsource (lib "") (part "CL21B104JBCNNNC"))
    )
    (comp (ref "C15")
      (value "22pF")
      (fields
        (field (name "BOM_Manufacturer Part") "CL10C220JB8NNNC")
        (field (name "BOM_Supplier Part") "C1653")
      )
      (libsource (lib "") (part "CL10C220JB8NNNC"))
    )
    (comp (ref "C16")
      (value "22pF")
      (fields
        (field (name "BOM_Manufacturer Part") "CL10C220JB8NNNC")
        (field (name "BOM_Supplier Part") "C1653")
      )
      (libsource (lib "") (part "CL10C220JB8NNNC"))
    )
    (comp (ref "C17")
      (value "10uF")
      (fields
        (field (name "BOM_Manufacturer Part") "CL31B106KOHNNNE")
        (field (name "BOM_Supplier Part") "C47971")
      )
      (libsource (lib "") (part "CL31B106KOHNNNE"))
    )
    (comp (ref "C18")
      (value "100nF")
      (fields
        (field (name "BOM_Manufacturer Part") "CL21B104JBCNNNC")
        (field (name "BOM_Supplier Part") "C62912")
      )
      (libsource (lib "") (part "CL21B104JBCNNNC"))
    )
    (comp (ref "D1")
      (value "STPS1H100AF")
      (fields (field (name "BOM_Supplier Part") "C361044"))
      (libsource (lib "") (part "STPS1H100AF"))
    )
    (comp (ref "DD2")
      (value "CH340G")
      (fields (field (name "BOM_Supplier Part") "C14267"))
      (libsource (lib "") (part "CH340G"))
    )
    (comp (ref "H1")
      (value "Header-Male-2.54_1x2")
      (fields (field (name "BOM_Manufacturer Part") "826629-2") (field (name "BOM_Supplier Part") "C86471"))
      (libsource (lib "") (part "Header-Male-2.54_1x2"))
    )
    (comp (ref "KEY1")
      (value "TSA063G50-250")
      (fields (field (name "BOM_Supplier Part") "C294565"))
      (libsource (lib "") (part "TSA063G50-250"))
    )
    (comp (ref "KEY2")
      (value "TSA063G50-250")
      (fields (field (name "BOM_Supplier Part") "C294565"))
      (libsource (lib "") (part "TSA063G50-250"))
    )
    (comp (ref "R14")
      (value "20K")
      (fields
        (field (name "BOM_Manufacturer Part") "0805W8F2002T5E")
        (field (name "BOM_Supplier Part") "C4328")
      )
      (libsource (lib "") (part "0805W8F2002T5E"))
    )
    (comp (ref "R15")
      (value "20K")
      (fields
        (field (name "BOM_Manufacturer Part") "0805W8F2002T5E")
        (field (name "BOM_Supplier Part") "C4328")
      )
      (libsource (lib "") (part "0805W8F2002T5E_1"))
    )
    (comp (ref "R16")
      (value "20K")
      (fields
        (field (name "BOM_Manufacturer Part") "0805W8F2002T5E")
        (field (name "BOM_Supplier Part") "C4328")
      )
      (libsource (lib "") (part "0805W8F2002T5E"))
    )
    (comp (ref "R17")
      (value "20K")
      (fields
        (field (name "BOM_Manufacturer Part") "0805W8F2002T5E")
        (field (name "BOM_Supplier Part") "C4328")
      )
      (libsource (lib "") (part "0805W8F2002T5E_2"))
    )
    (comp (ref "R18")
      (value "470")
      (fields
        (field (name "BOM_Manufacturer Part") "1206W4J0471T5E")
        (field (name "BOM_Supplier Part") "C25383")
      )
      (libsource (lib "") (part "1206W4J0471T5E"))
    )
    (comp (ref "R19")
      (value "470")
      (fields
        (field (name "BOM_Manufacturer Part") "1206W4J0471T5E")
        (field (name "BOM_Supplier Part") "C25383")
      )
      (libsource (lib "") (part "1206W4J0471T5E"))
    )
    (comp (ref "VT1")
      (value "PMBT5551,215")
      (fields (field (name "BOM_Supplier Part") "C75557"))
      (libsource (lib "") (part "PMBT5551,215"))
    )
    (comp (ref "VT2")
      (value "PMBT5551,215")
      (fields (field (name "BOM_Supplier Part") "C75557"))
      (libsource (lib "") (part "PMBT5551,215_1"))
    )
    (comp (ref "X2")
      (value "MICROXNJ")
      (fields (field (name "BOM_Manufacturer Part") "MicroXNJ") (field (name "BOM_Supplier Part") "C404969"))
      (libsource (lib "") (part "MICROXNJ"))
    )
    (comp (ref "ZQ1")
      (value "12MHz")
      (fields
        (field (name "BOM_Manufacturer Part") "HC-49S12MHz20pF30PPM")
        (field (name "BOM_Supplier Part") "C127674")
      )
      (libsource (lib "") (part "HC-49S12MHZ20PF30PPM"))
    )
    (comp (ref "C19")
      (value "22uF")
      (fields
        (field (name "BOM_Manufacturer Part") "CL21A226MQQNNNE")
        (field (name "BOM_Supplier Part") "C5674")
      )
      (libsource (lib "") (part "CL21A226MQQNNNE"))
    )
    (comp (ref "C20")
      (value "22uF")
      (fields
        (field (name "BOM_Manufacturer Part") "CL21A226MQQNNNE")
        (field (name "BOM_Supplier Part") "C5674")
      )
      (libsource (lib "") (part "CL21A226MQQNNNE"))
    )
    (comp (ref "D2")
      (value "STPS1H100AF")
      (fields (field (name "BOM_Supplier Part") "C361044"))
      (libsource (lib "") (part "STPS1H100AF"))
    )
    (comp (ref "DA1")
      (value "AMS1117-3.3_C426566")
      (fields
        (field (name "BOM_Manufacturer Part") "AMS1117-3.3")
        (field (name "BOM_Supplier Part") "C426566")
      )
      (libsource (lib "") (part "AMS1117-3.3_C426566"))
    )
    (comp (ref "H2")
      (value "Header-Male-2.54_1x2")
      (fields (field (name "BOM_Manufacturer Part") "826629-2") (field (name "BOM_Supplier Part") "C86471"))
      (libsource (lib "") (part "Header-Male-2.54_1x2"))
    )
    (comp (ref "LED1")
      (value "3528 Red LED")
      (fields (field (name "BOM_Supplier Part") "C2305"))
      (libsource (lib "") (part "3528 Red LED"))
    )
    (comp (ref "R20")
      (value "1K")
      (fields
        (field (name "BOM_Manufacturer Part") "TC0525F1001T5E")
        (field (name "BOM_Supplier Part") "C75781")
      )
      (libsource (lib "") (part "TC0525F1001T5E"))
    )
    (comp (ref "C35")
      (value "100nF")
      (fields
        (field (name "BOM_Manufacturer Part") "CL21B104JBCNNNC")
        (field (name "BOM_Supplier Part") "C62912")
      )
      (libsource (lib "") (part "CL21B104JBCNNNC"))
    )
    (comp (ref "C36")
      (value "100nF")
      (fields
        (field (name "BOM_Manufacturer Part") "CL21B104JBCNNNC")
        (field (name "BOM_Supplier Part") "C62912")
      )
      (libsource (lib "") (part "CL21B104JBCNNNC_1"))
    )
    (comp (ref "C37")
      (value "18pF")
      (fields
        (field (name "BOM_Manufacturer Part") "0402CG180J500NT")
        (field (name "BOM_Supplier Part") "C1549")
      )
      (libsource (lib "") (part "0402CG180J500NT_1"))
    )
    (comp (ref "C38")
      (value "18pF")
      (fields
        (field (name "BOM_Manufacturer Part") "0402CG180J500NT")
        (field (name "BOM_Supplier Part") "C1549")
      )
      (libsource (lib "") (part "0402CG180J500NT"))
    )
    (comp (ref "C40")
      (value "22uF")
      (fields
        (field (name "BOM_Manufacturer Part") "CL21A226MQQNNNE")
        (field (name "BOM_Supplier Part") "C5674")
      )
      (libsource (lib "") (part "CL21A226MQQNNNE"))
    )
    (comp (ref "C45")
      (value "22uF")
      (fields
        (field (name "BOM_Manufacturer Part") "CL21A226MQQNNNE")
        (field (name "BOM_Supplier Part") "C5674")
      )
      (libsource (lib "") (part "CL21A226MQQNNNE"))
    )
    (comp (ref "DD7")
      (value "ATMEGA328P-AU")
      (fields (field (name "BOM_Supplier Part") "C14877"))
      (libsource (lib "") (part "ATMEGA328P-AU"))
    )
    (comp (ref "KEY6")
      (value "TSA063G50-250")
      (fields (field (name "BOM_Supplier Part") "C294565"))
      (libsource (lib "") (part "TSA063G50-250"))
    )
    (comp (ref "R33")
      (value "10K")
      (fields
        (field (name "BOM_Manufacturer Part") "ARG03FTC1002")
        (field (name "BOM_Supplier Part") "C217687")
      )
      (libsource (lib "") (part "ARG03FTC1002"))
    )
    (comp (ref "X7")
      (value "HDR-IDC-2.54-2X10P")
      (fields
        (field (name "BOM_Manufacturer Part") "IDC Box 2.54mm 2X10P　Straight")
        (field (name "BOM_Supplier Part") "C3405")
      )
      (libsource (lib "") (part "HDR-IDC-2.54-2X10P"))
    )
    (comp (ref "X9")
      (value "Header-Male-2.54_2x3")
      (fields (field (name "BOM_Supplier Part") "C65114"))
      (libsource (lib "") (part "Header-Male-2.54_2x3"))
    )
    (comp (ref "ZQ5")
      (value "16MHz")
      (fields
        (field (name "BOM_Manufacturer Part") "X49SD16MSB2SI")
        (field (name "BOM_Supplier Part") "C188202")
      )
      (libsource (lib "") (part "X49SD16MSB2SI"))
    )
    (comp (ref "C30")
      (value "10uF")
      (fields
        (field (name "BOM_Manufacturer Part") "CL31B106KOHNNNE")
        (field (name "BOM_Supplier Part") "C47971")
      )
      (libsource (lib "") (part "CL31B106KOHNNNE"))
    )
    (comp (ref "C31")
      (value "18pF")
      (fields
        (field (name "BOM_Manufacturer Part") "0402CG180J500NT")
        (field (name "BOM_Supplier Part") "C1549")
      )
      (libsource (lib "") (part "0402CG180J500NT"))
    )
    (comp (ref "C32")
      (value "18pF")
      (fields
        (field (name "BOM_Manufacturer Part") "0402CG180J500NT")
        (field (name "BOM_Supplier Part") "C1549")
      )
      (libsource (lib "") (part "0402CG180J500NT"))
    )
    (comp (ref "C33")
      (value "10nF")
      (fields
        (field (name "BOM_Manufacturer Part") "CL21B103KBANNNC")
        (field (name "BOM_Supplier Part") "C1710")
      )
      (libsource (lib "") (part "CL21B103KBANNNC"))
    )
    (comp (ref "C34")
      (value "10nF")
      (fields
        (field (name "BOM_Manufacturer Part") "CL21B103KBANNNC")
        (field (name "BOM_Supplier Part") "C1710")
      )
      (libsource (lib "") (part "CL21B103KBANNNC"))
    )
    (comp (ref "DD4")
      (value "ENC28J60-I/SO")
      (fields (field (name "BOM_Supplier Part") "C47351"))
      (libsource (lib "") (part "ENC28J60-I/SO"))
    )
    (comp (ref "H3")
      (value "Header-Male-2.54_1x2")
      (fields (field (name "BOM_Manufacturer Part") "826629-2") (field (name "BOM_Supplier Part") "C86471"))
      (libsource (lib "") (part "Header-Male-2.54_1x2"))
    )
    (comp (ref "H4")
      (value "Header-Male-2.54_1x2")
      (fields (field (name "BOM_Manufacturer Part") "826629-2") (field (name "BOM_Supplier Part") "C86471"))
      (libsource (lib "") (part "Header-Male-2.54_1x2"))
    )
    (comp (ref "H5")
      (value "Header-Male-2.54_1x2")
      (fields (field (name "BOM_Manufacturer Part") "826629-2") (field (name "BOM_Supplier Part") "C86471"))
      (libsource (lib "") (part "Header-Male-2.54_1x2_1"))
    )
    (comp (ref "L1")
      (value "10uH")
      (fields
        (field (name "BOM_Manufacturer Part") "CMI321609X100KT")
        (field (name "BOM_Supplier Part") "C1051")
      )
      (libsource (lib "") (part "CMI321609X100KT"))
    )
    (comp (ref "R24")
      (value "2.32K")
      (fields
        (field (name "BOM_Manufacturer Part") "1206W4F2321T5E")
        (field (name "BOM_Supplier Part") "C247348")
      )
      (libsource (lib "") (part "1206W4F2321T5E"))
    )
    (comp (ref "R25")
      (value "10K")
      (fields
        (field (name "BOM_Manufacturer Part") "ARG03FTC1002")
        (field (name "BOM_Supplier Part") "C217687")
      )
      (libsource (lib "") (part "ARG03FTC1002"))
    )
    (comp (ref "R26")
      (value "10K")
      (fields
        (field (name "BOM_Manufacturer Part") "ARG03FTC1002")
        (field (name "BOM_Supplier Part") "C217687")
      )
      (libsource (lib "") (part "ARG03FTC1002"))
    )
    (comp (ref "R27")
      (value "49.9")
      (fields
        (field (name "BOM_Manufacturer Part") "0805W8F499JT5E")
        (field (name "BOM_Supplier Part") "C17720")
      )
      (libsource (lib "") (part "0805W8F499JT5E"))
    )
    (comp (ref "R28")
      (value "49.9")
      (fields
        (field (name "BOM_Manufacturer Part") "0805W8F499JT5E")
        (field (name "BOM_Supplier Part") "C17720")
      )
      (libsource (lib "") (part "0805W8F499JT5E"))
    )
    (comp (ref "R29")
      (value "49.9")
      (fields
        (field (name "BOM_Manufacturer Part") "0805W8F499JT5E")
        (field (name "BOM_Supplier Part") "C17720")
      )
      (libsource (lib "") (part "0805W8F499JT5E"))
    )
    (comp (ref "R30")
      (value "49.9")
      (fields
        (field (name "BOM_Manufacturer Part") "0805W8F499JT5E")
        (field (name "BOM_Supplier Part") "C17720")
      )
      (libsource (lib "") (part "0805W8F499JT5E"))
    )
    (comp (ref "R31")
      (value "510")
      (fields
        (field (name "BOM_Manufacturer Part") "1206W4J0511T5E")
        (field (name "BOM_Supplier Part") "C25386")
      )
      (libsource (lib "") (part "1206W4J0511T5E"))
    )
    (comp (ref "R32")
      (value "510")
      (fields
        (field (name "BOM_Manufacturer Part") "1206W4J0511T5E")
        (field (name "BOM_Supplier Part") "C25386")
      )
      (libsource (lib "") (part "1206W4J0511T5E"))
    )
    (comp (ref "X6")
      (value "HR911105A_C12074")
      (fields (field (name "BOM_Manufacturer Part") "HR911105A") (field (name "BOM_Supplier Part") "C12074"))
      (libsource (lib "") (part "HR911105A_C12074"))
    )
    (comp (ref "ZQ3")
      (value "25MHz")
      (fields
        (field (name "BOM_Manufacturer Part") "X49SD25MSD2SI")
        (field (name "BOM_Supplier Part") "C130152")
      )
      (libsource (lib "") (part "X49SD25MSD2SI"))
    )
  )
  (nets
    (net (code "1") (name "3v3") (class "Default")
      (node (ref "C20") (pin "1") (pinfunction "1_1") (pintype "unspecified"))
      (node (ref "C9") (pin "1") (pinfunction "1_1") (pintype "input"))
      (node (ref "DA1") (pin "2") (pinfunction "VOUT_2") (pintype "unspecified"))
      (node (ref "DA1") (pin "4") (pinfunction "VOUT_4") (pintype "unspecified"))
      (node (ref "DD4") (pin "15") (pinfunction "VDDTX_15") (pintype "unspecified"))
      (node (ref "DD4") (pin "19") (pinfunction "VDDRX_19") (pintype "unspecified"))
      (node (ref "DD4") (pin "20") (pinfunction "VDDPLL_20") (pintype "unspecified"))
      (node (ref "DD4") (pin "25") (pinfunction "VDDOSC_25") (pintype "unspecified"))
      (node (ref "DD4") (pin "28") (pinfunction "VDD_28") (pintype "unspecified"))
      (node (ref "L1") (pin "1") (pinfunction "1_1") (pintype "unspecified"))
      (node (ref "LED5") (pin "1") (pinfunction "A_1") (pintype "unspecified"))
      (node (ref "R16") (pin "2") (pinfunction "2_2") (pintype "input"))
      (node (ref "R17") (pin "2") (pinfunction "2_2") (pintype "input"))
      (node (ref "R25") (pin "2") (pinfunction "2_2") (pintype "unspecified"))
      (node (ref "R26") (pin "2") (pinfunction "2_2") (pintype "unspecified"))
      (node (ref "U1") (pin "2") (pinfunction "VCCA_2") (pintype "unspecified"))
    )
    (net (code "2") (name "5V") (class "Default")
      (node (ref "C17") (pin "2") (pinfunction "2_2") (pintype "input"))
      (node (ref "C18") (pin "2") (pinfunction "2_2") (pintype "input"))
      (node (ref "C19") (pin "1") (pinfunction "1_1") (pintype "unspecified"))
      (node (ref "C40") (pin "2") (pinfunction "2_2") (pintype "unspecified"))
      (node (ref "C45") (pin "1") (pinfunction "1_1") (pintype "unspecified"))
      (node (ref "D1") (pin "1") (pinfunction "K_1") (pintype "unspecified"))
      (node (ref "D2") (pin "1") (pinfunction "K_1") (pintype "unspecified"))
      (node (ref "DA1") (pin "3") (pinfunction "VIN_3") (pintype "unspecified"))
      (node (ref "DD2") (pin "16") (pinfunction "VCC_16") (pintype "unspecified"))
      (node (ref "DD7") (pin "18") (pinfunction "AVCC_18") (pintype "unspecified"))
      (node (ref "DD7") (pin "4") (pinfunction "VCC_4") (pintype "unspecified"))
      (node (ref "DD7") (pin "6") (pinfunction "VCC_6") (pintype "unspecified"))
      (node (ref "H2") (pin "1") (pinfunction "1_1") (pintype "unspecified"))
      (node (ref "R20") (pin "2") (pinfunction "2_2") (pintype "input"))
      (node (ref "R33") (pin "2") (pinfunction "2_2") (pintype "unspecified"))
      (node (ref "U1") (pin "19") (pinfunction "VCCB_19") (pintype "unspecified"))
      (node (ref "X9") (pin "2") (pinfunction "2_2") (pintype "input"))
    )
    (net (code "3") (name "5V_EXT") (class "Default")
      (node (ref "D2") (pin "2") (pinfunction "A_2") (pintype "unspecified"))
      (node (ref "H2") (pin "2") (pinfunction "2_2") (pintype "unspecified"))
      (node (ref "X1") (pin "1") (pinfunction "1_1") (pintype "unspecified"))
      (node (ref "X1") (pin "2") (pinfunction "2_2") (pintype "unspecified"))
    )
    (net (code "4") (name "AT_ADC6") (class "Default")
      (node (ref "DD7") (pin "19") (pinfunction "ADC6_19") (pintype "unspecified"))
    )
    (net (code "5") (name "AT_ADC7") (class "Default")
      (node (ref "DD7") (pin "22") (pinfunction "ADC7_22") (pintype "unspecified"))
      (node (ref "X7") (pin "16") (pinfunction "16_16") (pintype "unspecified"))
    )
    (net (code "6") (name "AT_BAT1") (class "Default")
      (node (ref "DD7") (pin "1") (pinfunction "(PCINT19/OC2B/INT1)PD3_1") (pintype "unspecified"))
      (node (ref "X7") (pin "1") (pinfunction "1_1") (pintype "unspecified"))
    )
    (net (code "7") (name "AT_BAT2") (class "Default")
      (node (ref "DD7") (pin "32") (pinfunction "PD2(INT0/PCINT18)_32") (pintype "unspecified"))
      (node (ref "X7") (pin "2") (pinfunction "2_2") (pintype "unspecified"))
    )
    (net (code "8") (name "AT_BAT3") (class "Default")
      (node (ref "DD7") (pin "2") (pinfunction "(PCINT20/XCK/T0)PD4_2") (pintype "unspecified"))
      (node (ref "X7") (pin "3") (pinfunction "3_3") (pintype "unspecified"))
    )
    (net (code "9") (name "AT_BAT4") (class "Default")
      (node (ref "DD7") (pin "28") (pinfunction "PC5(ADC5/SCL/PCINT13)_28") (pintype "unspecified"))
      (node (ref "X7") (pin "4") (pinfunction "4_4") (pintype "unspecified"))
    )
    (net (code "10") (name "AT_BAT5") (class "Default")
      (node (ref "DD7") (pin "9") (pinfunction "(PCINT21/OC0B/T1)PD5_9") (pintype "unspecified"))
      (node (ref "X7") (pin "5") (pinfunction "5_5") (pintype "unspecified"))
    )
    (net (code "11") (name "AT_BAT6") (class "Default")
      (node (ref "DD7") (pin "27") (pinfunction "PC4(ADC4/SDA/PCINT12)_27") (pintype "unspecified"))
      (node (ref "X7") (pin "6") (pinfunction "6_6") (pintype "unspecified"))
    )
    (net (code "12") (name "AT_BAT7") (class "Default")
      (node (ref "DD7") (pin "11") (pinfunction "(PCINT23/AIN1)PD7_11") (pintype "unspecified"))
      (node (ref "X7") (pin "7") (pinfunction "7_7") (pintype "unspecified"))
    )
    (net (code "13") (name "AT_BAT8") (class "Default")
      (node (ref "DD7") (pin "26") (pinfunction "PC3(ADC3/PCINT11)_26") (pintype "unspecified"))
      (node (ref "X7") (pin "8") (pinfunction "8_8") (pintype "unspecified"))
    )
    (net (code "14") (name "AT_BAT9") (class "Default")
      (node (ref "DD7") (pin "12") (pinfunction "(PCINT0/CLKO/ICP1)PB0_12") (pintype "unspecified"))
      (node (ref "X7") (pin "9") (pinfunction "9_9") (pintype "unspecified"))
    )
    (net (code "15") (name "AT_BAT10") (class "Default")
      (node (ref "DD7") (pin "25") (pinfunction "PC2(ADC2/PCINT10)_25") (pintype "unspecified"))
      (node (ref "X7") (pin "10") (pinfunction "10_10") (pintype "unspecified"))
    )
    (net (code "16") (name "AT_BAT11") (class "Default")
      (node (ref "DD7") (pin "24") (pinfunction "PC1(ADC1/PCINT9)_24") (pintype "unspecified"))
      (node (ref "X7") (pin "11") (pinfunction "11_11") (pintype "unspecified"))
    )
    (net (code "17") (name "AT_BAT12") (class "Default")
      (node (ref "DD7") (pin "23") (pinfunction "PC0(ADC0/PCINT8)_23") (pintype "unspecified"))
      (node (ref "X7") (pin "12") (pinfunction "12_12") (pintype "unspecified"))
    )
    (net (code "18") (name "AT_MISO") (class "Default")
      (node (ref "DD7") (pin "16") (pinfunction "(PCINT4/MISO)PB4_16") (pintype "unspecified"))
      (node (ref "X9") (pin "1") (pinfunction "1_1") (pintype "input"))
    )
    (net (code "19") (name "AT_MOSI") (class "Default")
      (node (ref "DD7") (pin "15") (pinfunction "(PCINT3/OC2A/MOSI)PB3_15") (pintype "unspecified"))
      (node (ref "X9") (pin "4") (pinfunction "4_4") (pintype "input"))
    )
    (net (code "20") (name "AT_OC0") (class "Default")
      (node (ref "DD7") (pin "10") (pinfunction "(PCINT22/OC0A/AIN0)PD6_10") (pintype "unspecified"))
      (node (ref "X7") (pin "14") (pinfunction "14_14") (pintype "unspecified"))
    )
    (net (code "21") (name "AT_OC1A") (class "Default")
      (node (ref "DD7") (pin "13") (pinfunction "(PCINT1/OC1A)PB1_13") (pintype "unspecified"))
      (node (ref "X7") (pin "18") (pinfunction "18_18") (pintype "unspecified"))
    )
    (net (code "22") (name "AT_OC1B") (class "Default")
      (node (ref "DD7") (pin "14") (pinfunction "(PCINT2/SS#/OC1B)PB2_14") (pintype "unspecified"))
      (node (ref "X7") (pin "20") (pinfunction "20_20") (pintype "unspecified"))
    )
    (net (code "23") (name "AT_RESET") (class "Default")
      (node (ref "C36") (pin "2") (pinfunction "2_2") (pintype "input"))
      (node (ref "DD7") (pin "29") (pinfunction "PC6(RESET#/PCINT14)_29") (pintype "unspecified"))
      (node (ref "KEY6") (pin "3") (pinfunction "3_3") (pintype "unspecified"))
      (node (ref "R33") (pin "1") (pinfunction "1_1") (pintype "unspecified"))
      (node (ref "X9") (pin "5") (pinfunction "5_5") (pintype "input"))
    )
    (net (code "24") (name "AT_RXD0") (class "Default")
      (node (ref "DD7") (pin "30") (pinfunction "PD0(RXD/PCINT16)_30") (pintype "unspecified"))
      (node (ref "U1") (pin "18") (pinfunction "B2_18") (pintype "unspecified"))
    )
    (net (code "25") (name "AT_SCK") (class "Default")
      (node (ref "DD7") (pin "17") (pinfunction "PB5(SCK/PCINT5)_17") (pintype "unspecified"))
      (node (ref "X9") (pin "3") (pinfunction "3_3") (pintype "input"))
    )
    (net (code "26") (name "AT_TXD0") (class "Default")
      (node (ref "DD7") (pin "31") (pinfunction "PD1(TXD/PCINT17)_31") (pintype "unspecified"))
      (node (ref "U1") (pin "20") (pinfunction "B1_20") (pintype "unspecified"))
    )
    (net (code "27") (name "CLKOUT") (class "Default")
      (node (ref "DD4") (pin "3") (pinfunction "CLKOUT_3") (pintype "unspecified"))
      (node (ref "H5") (pin "2") (pinfunction "2_2") (pintype "unspecified"))
    )
    (net (code "28") (name "CS") (class "Default")
      (node (ref "DD1") (pin "36") (pinfunction "IO22_36") (pintype "unspecified"))
      (node (ref "DD4") (pin "9") (pinfunction "CS#_9") (pintype "unspecified"))
      (node (ref "H4") (pin "2") (pinfunction "2_2") (pintype "unspecified"))
      (node (ref "R26") (pin "1") (pinfunction "1_1") (pintype "unspecified"))
    )
    (net (code "29") (name "DTR") (class "Default")
      (node (ref "DD2") (pin "13") (pinfunction "DTR#_13") (pintype "unspecified"))
      (node (ref "R14") (pin "1") (pinfunction "1_1") (pintype "input"))
      (node (ref "VT2") (pin "2") (pinfunction "2_2") (pintype "input"))
    )
    (net (code "30") (name "ESP_EN") (class "Default")
      (node (ref "C10") (pin "2") (pinfunction "2_2") (pintype "input"))
      (node (ref "C12") (pin "2") (pinfunction "2_2") (pintype "input"))
      (node (ref "DD1") (pin "3") (pinfunction "EN_3") (pintype "unspecified"))
      (node (ref "KEY1") (pin "2") (pinfunction "2_2") (pintype "unspecified"))
      (node (ref "R16") (pin "1") (pinfunction "1_1") (pintype "input"))
      (node (ref "VT1") (pin "3") (pinfunction "3_3") (pintype "input"))
    )
    (net (code "31") (name "ESP_IO0") (class "Default")
      (node (ref "C11") (pin "2") (pinfunction "2_2") (pintype "input"))
      (node (ref "C13") (pin "2") (pinfunction "2_2") (pintype "input"))
      (node (ref "DD1") (pin "25") (pinfunction "IO0_25") (pintype "unspecified"))
      (node (ref "H1") (pin "1") (pinfunction "1_1") (pintype "unspecified"))
      (node (ref "KEY2") (pin "2") (pinfunction "2_2") (pintype "unspecified"))
      (node (ref "VT2") (pin "3") (pinfunction "3_3") (pintype "input"))
    )
    (net (code "32") (name "ESP_IO2") (class "Default")
      (node (ref "DD1") (pin "24") (pinfunction "IO2_24") (pintype "unspecified"))
      (node (ref "KEY3") (pin "3") (pinfunction "3_3") (pintype "unspecified"))
    )
    (net (code "33") (name "ESP_IO4") (class "Default")
      (node (ref "DD1") (pin "26") (pinfunction "IO4_26") (pintype "unspecified"))
      (node (ref "DD4") (pin "4") (pinfunction "INT#_4") (pintype "unspecified"))
    )
    (net (code "34") (name "ESP_IO5") (class "Default")
      (node (ref "DD1") (pin "29") (pinfunction "IO5_29") (pintype "unspecified"))
      (node (ref "H4") (pin "1") (pinfunction "1_1") (pintype "unspecified"))
    )
    (net (code "35") (name "ESP_IO12") (class "Default")
      (node (ref "C44") (pin "1") (pinfunction "1_1") (pintype "input"))
      (node (ref "DD1") (pin "14") (pinfunction "IO12_14") (pintype "unspecified"))
      (node (ref "R36") (pin "2") (pinfunction "2_2") (pintype "input"))
      (node (ref "R37") (pin "1") (pinfunction "1_1") (pintype "input"))
    )
    (net (code "36") (name "ESP_IO13") (class "Default")
      (node (ref "DD1") (pin "16") (pinfunction "IO13_16") (pintype "unspecified"))
      (node (ref "R35") (pin "1") (pinfunction "1_1") (pintype "input"))
    )
    (net (code "37") (name "ESP_IO14") (class "Default")
      (node (ref "DD1") (pin "13") (pinfunction "IO14_13") (pintype "unspecified"))
      (node (ref "X1") (pin "20") (pinfunction "20_20") (pintype "unspecified"))
    )
    (net (code "38") (name "ESP_IO15") (class "Default")
      (node (ref "DD1") (pin "23") (pinfunction "IO15_23") (pintype "unspecified"))
      (node (ref "KEY4") (pin "2") (pinfunction "2_2") (pintype "unspecified"))
    )
    (net (code "39") (name "ESP_IO18") (class "Default")
      (node (ref "DD1") (pin "30") (pinfunction "IO18_30") (pintype "unspecified"))
      (node (ref "H3") (pin "1") (pinfunction "1_1") (pintype "unspecified"))
    )
    (net (code "40") (name "ESP_IO19") (class "Default")
      (node (ref "DD1") (pin "31") (pinfunction "IO19_31") (pintype "unspecified"))
      (node (ref "DD4") (pin "8") (pinfunction "SCK_8") (pintype "unspecified"))
    )
    (net (code "41") (name "ESP_IO21") (class "Default")
      (node (ref "C9") (pin "2") (pinfunction "2_2") (pintype "input"))
      (node (ref "DD1") (pin "33") (pinfunction "IO21_33") (pintype "unspecified"))
      (node (ref "R13") (pin "2") (pinfunction "2_2") (pintype "unspecified"))
      (node (ref "U1") (pin "10") (pinfunction "OE_10") (pintype "unspecified"))
    )
    (net (code "42") (name "ESP_IO23") (class "Default")
      (node (ref "DD1") (pin "37") (pinfunction "IO23_37") (pintype "unspecified"))
      (node (ref "DD4") (pin "7") (pinfunction "SI_7") (pintype "unspecified"))
    )
    (net (code "43") (name "ESP_IO25") (class "Default")
      (node (ref "DD1") (pin "10") (pinfunction "IO25_10") (pintype "unspecified"))
      (node (ref "DD4") (pin "6") (pinfunction "SO_6") (pintype "unspecified"))
    )
    (net (code "44") (name "ESP_IO26") (class "Default")
      (node (ref "DD1") (pin "11") (pinfunction "IO26_11") (pintype "unspecified"))
      (node (ref "X1") (pin "16") (pinfunction "16_16") (pintype "unspecified"))
    )
    (net (code "45") (name "ESP_IO27") (class "Default")
      (node (ref "DD1") (pin "12") (pinfunction "IO27_12") (pintype "unspecified"))
      (node (ref "X1") (pin "18") (pinfunction "18_18") (pintype "unspecified"))
    )
    (net (code "46") (name "ESP_IO32") (class "Default")
      (node (ref "C4") (pin "1") (pinfunction "1_1") (pintype "input"))
      (node (ref "DD1") (pin "8") (pinfunction "IO32_8") (pintype "unspecified"))
      (node (ref "R10") (pin "1") (pinfunction "1_1") (pintype "input"))
      (node (ref "R9") (pin "2") (pinfunction "2_2") (pintype "unspecified"))
    )
    (net (code "47") (name "ESP_IO33") (class "Default")
      (node (ref "C2") (pin "1") (pinfunction "1_1") (pintype "input"))
      (node (ref "DD1") (pin "9") (pinfunction "IO33_9") (pintype "unspecified"))
      (node (ref "R7") (pin "2") (pinfunction "2_2") (pintype "unspecified"))
      (node (ref "R8") (pin "1") (pinfunction "1_1") (pintype "input"))
    )
    (net (code "48") (name "ESP_IO34") (class "Default")
      (node (ref "C5") (pin "1") (pinfunction "1_1") (pintype "input"))
      (node (ref "DD1") (pin "6") (pinfunction "IO34_6") (pintype "unspecified"))
      (node (ref "R5") (pin "2") (pinfunction "2_2") (pintype "unspecified"))
      (node (ref "R6") (pin "1") (pinfunction "1_1") (pintype "input"))
    )
    (net (code "49") (name "ESP_IO35") (class "Default")
      (node (ref "C6") (pin "1") (pinfunction "1_1") (pintype "input"))
      (node (ref "DD1") (pin "7") (pinfunction "IO35_7") (pintype "unspecified"))
      (node (ref "R11") (pin "2") (pinfunction "2_2") (pintype "unspecified"))
      (node (ref "R12") (pin "1") (pinfunction "1_1") (pintype "input"))
    )
    (net (code "50") (name "ESP_IO36") (class "Default")
      (node (ref "C1") (pin "1") (pinfunction "1_1") (pintype "input"))
      (node (ref "DD1") (pin "4") (pinfunction "SENSOR_VP_4") (pintype "unspecified"))
      (node (ref "R22") (pin "1") (pinfunction "1_1") (pintype "input"))
      (node (ref "R23") (pin "2") (pinfunction "2_2") (pintype "unspecified"))
    )
    (net (code "51") (name "ESP_IO39") (class "Default")
      (node (ref "C3") (pin "1") (pinfunction "1_1") (pintype "input"))
      (node (ref "DD1") (pin "5") (pinfunction "SENSOR_VN_5") (pintype "unspecified"))
      (node (ref "R3") (pin "2") (pinfunction "2_2") (pintype "unspecified"))
      (node (ref "R4") (pin "1") (pinfunction "1_1") (pintype "input"))
    )
    (net (code "52") (name "ESP_RXD0") (class "Default")
      (node (ref "DD1") (pin "34") (pinfunction "RXD0_34") (pintype "unspecified"))
      (node (ref "R19") (pin "2") (pinfunction "2_2") (pintype "input"))
    )
    (net (code "53") (name "ESP_TXD0") (class "Default")
      (node (ref "DD1") (pin "35") (pinfunction "TXD0_35") (pintype "unspecified"))
      (node (ref "R18") (pin "2") (pinfunction "2_2") (pintype "input"))
    )
    (net (code "54") (name "ESP_U2RXD") (class "Default")
      (node (ref "DD1") (pin "27") (pinfunction "IO16_27") (pintype "unspecified"))
      (node (ref "U1") (pin "1") (pinfunction "A1_1") (pintype "unspecified"))
    )
    (net (code "55") (name "ESP_U2TXD") (class "Default")
      (node (ref "DD1") (pin "28") (pinfunction "IO17_28") (pintype "unspecified"))
      (node (ref "U1") (pin "3") (pinfunction "A2_3") (pintype "unspecified"))
    )
    (net (code "56") (name "GND") (class "Default")
      (node (ref "C1") (pin "2") (pinfunction "2_2") (pintype "input"))
      (node (ref "C10") (pin "1") (pinfunction "1_1") (pintype "input"))
      (node (ref "C11") (pin "1") (pinfunction "1_1") (pintype "input"))
      (node (ref "C14") (pin "1") (pinfunction "1_1") (pintype "input"))
      (node (ref "C15") (pin "1") (pinfunction "1_1") (pintype "input"))
      (node (ref "C16") (pin "1") (pinfunction "1_1") (pintype "input"))
      (node (ref "C17") (pin "1") (pinfunction "1_1") (pintype "input"))
      (node (ref "C18") (pin "1") (pinfunction "1_1") (pintype "input"))
      (node (ref "C19") (pin "2") (pinfunction "2_2") (pintype "unspecified"))
      (node (ref "C2") (pin "2") (pinfunction "2_2") (pintype "input"))
      (node (ref "C20") (pin "2") (pinfunction "2_2") (pintype "unspecified"))
      (node (ref "C21") (pin "1") (pinfunction "1_1") (pintype "input"))
      (node (ref "C22") (pin "1") (pinfunction "1_1") (pintype "input"))
      (node (ref "C3") (pin "2") (pinfunction "2_2") (pintype "input"))
      (node (ref "C30") (pin "2") (pinfunction "2_2") (pintype "input"))
      (node (ref "C31") (pin "2") (pinfunction "2_2") (pintype "input"))
      (node (ref "C32") (pin "2") (pinfunction "2_2") (pintype "input"))
      (node (ref "C33") (pin "2") (pinfunction "2_2") (pintype "input"))
      (node (ref "C34") (pin "2") (pinfunction "2_2") (pintype "input"))
      (node (ref "C35") (pin "2") (pinfunction "2_2") (pintype "input"))
      (node (ref "C36") (pin "1") (pinfunction "1_1") (pintype "input"))
      (node (ref "C37") (pin "2") (pinfunction "2_2") (pintype "input"))
      (node (ref "C38") (pin "1") (pinfunction "1_1") (pintype "input"))
      (node (ref "C4") (pin "2") (pinfunction "2_2") (pintype "input"))
      (node (ref "C40") (pin "1") (pinfunction "1_1") (pintype "unspecified"))
      (node (ref "C44") (pin "2") (pinfunction "2_2") (pintype "input"))
      (node (ref "C45") (pin "2") (pinfunction "2_2") (pintype "unspecified"))
      (node (ref "C5") (pin "2") (pinfunction "2_2") (pintype "input"))
      (node (ref "C6") (pin "2") (pinfunction "2_2") (pintype "input"))
      (node (ref "C7") (pin "1") (pinfunction "1_1") (pintype "input"))
      (node (ref "C8") (pin "2") (pinfunction "2_2") (pintype "unspecified"))
      (node (ref "DA1") (pin "1") (pinfunction "ADJ/GND_1") (pintype "unspecified"))
      (node (ref "DD1") (pin "1") (pinfunction "GND_1") (pintype "unspecified"))
      (node (ref "DD1") (pin "15") (pinfunction "GND_15") (pintype "unspecified"))
      (node (ref "DD1") (pin "38") (pinfunction "GND_38") (pintype "unspecified"))
      (node (ref "DD1") (pin "39") (pinfunction "GND_39") (pintype "unspecified"))
      (node (ref "DD2") (pin "1") (pinfunction "GND_1") (pintype "unspecified"))
      (node (ref "DD4") (pin "11") (pinfunction "VSSRX_11") (pintype "unspecified"))
      (node (ref "DD4") (pin "18") (pinfunction "VSSTX_18") (pintype "unspecified"))
      (node (ref "DD4") (pin "2") (pinfunction "VSS_2") (pintype "unspecified"))
      (node (ref "DD4") (pin "21") (pinfunction "VSSPLL_21") (pintype "unspecified"))
      (node (ref "DD4") (pin "22") (pinfunction "VSSOSC_22") (pintype "unspecified"))
      (node (ref "DD7") (pin "21") (pinfunction "GND_21") (pintype "unspecified"))
      (node (ref "DD7") (pin "3") (pinfunction "GND_3") (pintype "unspecified"))
      (node (ref "DD7") (pin "5") (pinfunction "GND_5") (pintype "unspecified"))
      (node (ref "H5") (pin "1") (pinfunction "1_1") (pintype "unspecified"))
      (node (ref "KEY1") (pin "4") (pinfunction "4_4") (pintype "unspecified"))
      (node (ref "KEY2") (pin "4") (pinfunction "4_4") (pintype "unspecified"))
      (node (ref "KEY3") (pin "4") (pinfunction "4_4") (pintype "unspecified"))
      (node (ref "KEY4") (pin "1") (pinfunction "1_1") (pintype "unspecified"))
      (node (ref "KEY6") (pin "1") (pinfunction "1_1") (pintype "unspecified"))
      (node (ref "LED1") (pin "2") (pinfunction "K_2") (pintype "unspecified"))
      (node (ref "R11") (pin "1") (pinfunction "1_1") (pintype "unspecified"))
      (node (ref "R13") (pin "1") (pinfunction "1_1") (pintype "unspecified"))
      (node (ref "R22") (pin "2") (pinfunction "2_2") (pintype "input"))
      (node (ref "R24") (pin "1") (pinfunction "1_1") (pintype "unspecified"))
      (node (ref "R36") (pin "1") (pinfunction "1_1") (pintype "input"))
      (node (ref "R4") (pin "2") (pinfunction "2_2") (pintype "input"))
      (node (ref "R6") (pin "2") (pinfunction "2_2") (pintype "input"))
      (node (ref "R7") (pin "1") (pinfunction "1_1") (pintype "unspecified"))
      (node (ref "R9") (pin "1") (pinfunction "1_1") (pintype "unspecified"))
      (node (ref "U1") (pin "11") (pinfunction "GND_11") (pintype "unspecified"))
      (node (ref "X1") (pin "11") (pinfunction "11_11") (pintype "unspecified"))
      (node (ref "X1") (pin "13") (pinfunction "13_13") (pintype "unspecified"))
      (node (ref "X1") (pin "15") (pinfunction "15_15") (pintype "unspecified"))
      (node (ref "X1") (pin "17") (pinfunction "17_17") (pintype "unspecified"))
      (node (ref "X1") (pin "3") (pinfunction "3_3") (pintype "unspecified"))
      (node (ref "X1") (pin "5") (pinfunction "5_5") (pintype "unspecified"))
      (node (ref "X1") (pin "7") (pinfunction "7_7") (pintype "unspecified"))
      (node (ref "X1") (pin "9") (pinfunction "9_9") (pintype "unspecified"))
      (node (ref "X2") (pin "5") (pinfunction "GND_5") (pintype "unspecified"))
      (node (ref "X2") (pin "6") (pinfunction "SH1_6") (pintype "unspecified"))
      (node (ref "X2") (pin "7") (pinfunction "SH2_7") (pintype "unspecified"))
      (node (ref "X2") (pin "8") (pinfunction "SH3_8") (pintype "unspecified"))
      (node (ref "X2") (pin "9") (pinfunction "SH4_9") (pintype "unspecified"))
      (node (ref "X6") (pin "10") (pinfunction "10_10") (pintype "unspecified"))
      (node (ref "X6") (pin "11") (pinfunction "11_11") (pintype "unspecified"))
      (node (ref "X6") (pin "SH1") (pinfunction "SH1_SH1") (pintype "unspecified"))
      (node (ref "X6") (pin "SH2") (pinfunction "SH2_SH2") (pintype "unspecified"))
      (node (ref "X7") (pin "13") (pinfunction "13_13") (pintype "unspecified"))
      (node (ref "X7") (pin "15") (pinfunction "15_15") (pintype "unspecified"))
      (node (ref "X7") (pin "17") (pinfunction "17_17") (pintype "unspecified"))
      (node (ref "X7") (pin "19") (pinfunction "19_19") (pintype "unspecified"))
      (node (ref "X9") (pin "6") (pinfunction "6_6") (pintype "input"))
    )
    (net (code "57") (name "LEDA") (class "Default")
      (node (ref "R31") (pin "2") (pinfunction "2_2") (pintype "input"))
      (node (ref "X6") (pin "9") (pinfunction "9_9") (pintype "unspecified"))
    )
    (net (code "58") (name "LEDB") (class "Default")
      (node (ref "R32") (pin "2") (pinfunction "2_2") (pintype "input"))
      (node (ref "X6") (pin "12") (pinfunction "12_12") (pintype "unspecified"))
    )
    (net (code "59") (name "Net-(C12-Pad1)") (class "Default")
      (node (ref "C12") (pin "1") (pinfunction "1_1") (pintype "input"))
      (node (ref "KEY1") (pin "1") (pinfunction "1_1") (pintype "unspecified"))
    )
    (net (code "60") (name "Net-(C13-Pad1)") (class "Default")
      (node (ref "C13") (pin "1") (pinfunction "1_1") (pintype "input"))
      (node (ref "KEY2") (pin "1") (pinfunction "1_1") (pintype "unspecified"))
    )
    (net (code "61") (name "Net-(C21-Pad2)") (class "Default")
      (node (ref "C21") (pin "2") (pinfunction "2_2") (pintype "input"))
      (node (ref "KEY3") (pin "2") (pinfunction "2_2") (pintype "unspecified"))
    )
    (net (code "62") (name "Net-(C22-Pad2)") (class "Default")
      (node (ref "C22") (pin "2") (pinfunction "2_2") (pintype "input"))
      (node (ref "KEY4") (pin "3") (pinfunction "3_3") (pintype "unspecified"))
    )
    (net (code "63") (name "Net-(C33-Pad1)") (class "Default")
      (node (ref "C33") (pin "1") (pinfunction "1_1") (pintype "input"))
      (node (ref "R27") (pin "1") (pinfunction "1_1") (pintype "input"))
      (node (ref "R28") (pin "2") (pinfunction "2_2") (pintype "input"))
      (node (ref "X6") (pin "5") (pinfunction "5_5") (pintype "unspecified"))
    )
    (net (code "64") (name "Net-(C34-Pad1)") (class "Default")
      (node (ref "C34") (pin "1") (pinfunction "1_1") (pintype "input"))
      (node (ref "L1") (pin "2") (pinfunction "2_2") (pintype "unspecified"))
      (node (ref "R29") (pin "1") (pinfunction "1_1") (pintype "input"))
      (node (ref "R30") (pin "2") (pinfunction "2_2") (pintype "input"))
      (node (ref "X6") (pin "4") (pinfunction "4_4") (pintype "unspecified"))
    )
    (net (code "65") (name "Net-(D1-A)") (class "Default")
      (node (ref "D1") (pin "2") (pinfunction "A_2") (pintype "unspecified"))
      (node (ref "X2") (pin "1") (pinfunction "VBUS_1") (pintype "unspecified"))
    )
    (net (code "66") (name "Net-(DD1-VDD33)") (class "Default")
      (node (ref "C7") (pin "2") (pinfunction "2_2") (pintype "input"))
      (node (ref "C8") (pin "1") (pinfunction "1_1") (pintype "unspecified"))
      (node (ref "DD1") (pin "2") (pinfunction "VDD33_2") (pintype "unspecified"))
    )
    (net (code "67") (name "Net-(DD2-RXD)") (class "Default")
      (node (ref "DD2") (pin "3") (pinfunction "RXD_3") (pintype "unspecified"))
      (node (ref "R18") (pin "1") (pinfunction "1_1") (pintype "input"))
    )
    (net (code "68") (name "Net-(DD2-TXD)") (class "Default")
      (node (ref "DD2") (pin "2") (pinfunction "TXD_2") (pintype "unspecified"))
      (node (ref "R19") (pin "1") (pinfunction "1_1") (pintype "input"))
    )
    (net (code "69") (name "Net-(DD2-UD+)") (class "Default")
      (node (ref "DD2") (pin "5") (pinfunction "UD+_5") (pintype "unspecified"))
      (node (ref "X2") (pin "3") (pinfunction "D+_3") (pintype "unspecified"))
    )
    (net (code "70") (name "Net-(DD2-UD-)") (class "Default")
      (node (ref "DD2") (pin "6") (pinfunction "UD-_6") (pintype "unspecified"))
      (node (ref "X2") (pin "2") (pinfunction "D-_2") (pintype "unspecified"))
    )
    (net (code "71") (name "Net-(DD2-V3)") (class "Default")
      (node (ref "C14") (pin "2") (pinfunction "2_2") (pintype "input"))
      (node (ref "DD2") (pin "4") (pinfunction "V3_4") (pintype "unspecified"))
    )
    (net (code "72") (name "Net-(DD2-XI)") (class "Default")
      (node (ref "C15") (pin "2") (pinfunction "2_2") (pintype "input"))
      (node (ref "DD2") (pin "7") (pinfunction "XI_7") (pintype "unspecified"))
      (node (ref "ZQ1") (pin "1") (pinfunction "1_1") (pintype "unspecified"))
    )
    (net (code "73") (name "Net-(DD2-XO)") (class "Default")
      (node (ref "C16") (pin "2") (pinfunction "2_2") (pintype "input"))
      (node (ref "DD2") (pin "8") (pinfunction "XO_8") (pintype "unspecified"))
      (node (ref "ZQ1") (pin "2") (pinfunction "2_2") (pintype "unspecified"))
    )
    (net (code "74") (name "Net-(DD4-LEDA)") (class "Default")
      (node (ref "DD4") (pin "27") (pinfunction "LEDA_27") (pintype "unspecified"))
      (node (ref "R31") (pin "1") (pinfunction "1_1") (pintype "input"))
    )
    (net (code "75") (name "Net-(DD4-LEDB)") (class "Default")
      (node (ref "DD4") (pin "26") (pinfunction "LEDB_26") (pintype "unspecified"))
      (node (ref "R32") (pin "1") (pinfunction "1_1") (pintype "input"))
    )
    (net (code "76") (name "Net-(DD4-OSC1)") (class "Default")
      (node (ref "C31") (pin "1") (pinfunction "1_1") (pintype "input"))
      (node (ref "DD4") (pin "23") (pinfunction "OSC1_23") (pintype "unspecified"))
      (node (ref "ZQ3") (pin "1") (pinfunction "1_1") (pintype "unspecified"))
    )
    (net (code "77") (name "Net-(DD4-OSC2)") (class "Default")
      (node (ref "C32") (pin "1") (pinfunction "1_1") (pintype "input"))
      (node (ref "DD4") (pin "24") (pinfunction "OSC2_24") (pintype "unspecified"))
      (node (ref "ZQ3") (pin "2") (pinfunction "2_2") (pintype "unspecified"))
    )
    (net (code "78") (name "Net-(DD4-RBIAS)") (class "Default")
      (node (ref "DD4") (pin "14") (pinfunction "RBIAS_14") (pintype "unspecified"))
      (node (ref "R24") (pin "2") (pinfunction "2_2") (pintype "unspecified"))
    )
    (net (code "79") (name "Net-(DD4-VCAP)") (class "Default")
      (node (ref "C30") (pin "1") (pinfunction "1_1") (pintype "input"))
      (node (ref "DD4") (pin "1") (pinfunction "VCAP_1") (pintype "unspecified"))
    )
    (net (code "80") (name "Net-(DD7-(PCINT6{slash}XTAL1{slash}TOSC1)PB6)") (class "Default")
      (node (ref "C37") (pin "1") (pinfunction "1_1") (pintype "input"))
      (node (ref "DD7") (pin "7") (pinfunction "(PCINT6/XTAL1/TOSC1)PB6_7") (pintype "unspecified"))
      (node (ref "ZQ5") (pin "2") (pinfunction "OSC2_2") (pintype "input"))
    )
    (net (code "81") (name "Net-(DD7-(PCINT7{slash}XTAL2{slash}TOSC2)PB7)") (class "Default")
      (node (ref "C38") (pin "2") (pinfunction "2_2") (pintype "input"))
      (node (ref "DD7") (pin "8") (pinfunction "(PCINT7/XTAL2/TOSC2)PB7_8") (pintype "unspecified"))
      (node (ref "ZQ5") (pin "1") (pinfunction "OSC1_1") (pintype "input"))
    )
    (net (code "82") (name "Net-(DD7-AREF)") (class "Default")
      (node (ref "C35") (pin "1") (pinfunction "1_1") (pintype "input"))
      (node (ref "DD7") (pin "20") (pinfunction "AREF_20") (pintype "unspecified"))
    )
    (net (code "83") (name "Net-(H1-Pad2)") (class "Default")
      (node (ref "H1") (pin "2") (pinfunction "2_2") (pintype "unspecified"))
      (node (ref "R17") (pin "1") (pinfunction "1_1") (pintype "input"))
    )
    (net (code "84") (name "Net-(LED1-A)") (class "Default")
      (node (ref "LED1") (pin "1") (pinfunction "A_1") (pintype "unspecified"))
      (node (ref "R20") (pin "1") (pinfunction "1_1") (pintype "input"))
    )
    (net (code "85") (name "Net-(LED5-K)") (class "Default")
      (node (ref "LED5") (pin "2") (pinfunction "K_2") (pintype "unspecified"))
      (node (ref "R35") (pin "2") (pinfunction "2_2") (pintype "input"))
    )
    (net (code "86") (name "Net-(R3-Pad1)") (class "Default")
      (node (ref "R3") (pin "1") (pinfunction "1_1") (pintype "unspecified"))
      (node (ref "X1") (pin "6") (pinfunction "6_6") (pintype "unspecified"))
    )
    (net (code "87") (name "Net-(R5-Pad1)") (class "Default")
      (node (ref "R5") (pin "1") (pinfunction "1_1") (pintype "unspecified"))
      (node (ref "X1") (pin "8") (pinfunction "8_8") (pintype "unspecified"))
    )
    (net (code "88") (name "Net-(R8-Pad2)") (class "Default")
      (node (ref "R8") (pin "2") (pinfunction "2_2") (pintype "input"))
      (node (ref "X1") (pin "14") (pinfunction "14_14") (pintype "unspecified"))
    )
    (net (code "89") (name "Net-(R10-Pad2)") (class "Default")
      (node (ref "R10") (pin "2") (pinfunction "2_2") (pintype "input"))
      (node (ref "X1") (pin "12") (pinfunction "12_12") (pintype "unspecified"))
    )
    (net (code "90") (name "Net-(R12-Pad2)") (class "Default")
      (node (ref "R12") (pin "2") (pinfunction "2_2") (pintype "input"))
      (node (ref "X1") (pin "10") (pinfunction "10_10") (pintype "unspecified"))
    )
    (net (code "91") (name "Net-(R14-Pad2)") (class "Default")
      (node (ref "R14") (pin "2") (pinfunction "2_2") (pintype "input"))
      (node (ref "VT1") (pin "1") (pinfunction "1_1") (pintype "input"))
    )
    (net (code "92") (name "Net-(R15-Pad1)") (class "Default")
      (node (ref "R15") (pin "1") (pinfunction "1_1") (pintype "input"))
      (node (ref "VT2") (pin "1") (pinfunction "1_1") (pintype "input"))
    )
    (net (code "93") (name "Net-(R23-Pad1)") (class "Default")
      (node (ref "R23") (pin "1") (pinfunction "1_1") (pintype "unspecified"))
      (node (ref "X1") (pin "4") (pinfunction "4_4") (pintype "unspecified"))
    )
    (net (code "94") (name "Net-(R37-Pad2)") (class "Default")
      (node (ref "R37") (pin "2") (pinfunction "2_2") (pintype "input"))
      (node (ref "X1") (pin "19") (pinfunction "19_19") (pintype "unspecified"))
    )
    (net (code "95") (name "RESET") (class "Default")
      (node (ref "DD4") (pin "10") (pinfunction "RESET#_10") (pintype "unspecified"))
      (node (ref "H3") (pin "2") (pinfunction "2_2") (pintype "unspecified"))
      (node (ref "R25") (pin "1") (pinfunction "1_1") (pintype "unspecified"))
    )
    (net (code "96") (name "RTS") (class "Default")
      (node (ref "DD2") (pin "14") (pinfunction "RTS#_14") (pintype "unspecified"))
      (node (ref "R15") (pin "2") (pinfunction "2_2") (pintype "input"))
      (node (ref "VT1") (pin "2") (pinfunction "2_2") (pintype "input"))
    )
    (net (code "97") (name "TPIN+") (class "Default")
      (node (ref "DD4") (pin "13") (pinfunction "TPIN+_13") (pintype "unspecified"))
      (node (ref "R28") (pin "1") (pinfunction "1_1") (pintype "input"))
      (node (ref "X6") (pin "3") (pinfunction "RD+_3") (pintype "unspecified"))
    )
    (net (code "98") (name "TPIN-") (class "Default")
      (node (ref "DD4") (pin "12") (pinfunction "TPIN-_12") (pintype "unspecified"))
      (node (ref "R27") (pin "2") (pinfunction "2_2") (pintype "input"))
      (node (ref "X6") (pin "6") (pinfunction "RD-_6") (pintype "unspecified"))
    )
    (net (code "99") (name "TPOUT+") (class "Default")
      (node (ref "DD4") (pin "17") (pinfunction "TPOUT+_17") (pintype "unspecified"))
      (node (ref "R30") (pin "1") (pinfunction "1_1") (pintype "input"))
      (node (ref "X6") (pin "1") (pinfunction "TD+_1") (pintype "unspecified"))
    )
    (net (code "100") (name "TPOUT-") (class "Default")
      (node (ref "DD4") (pin "16") (pinfunction "TPOUT-_16") (pintype "unspecified"))
      (node (ref "R29") (pin "2") (pinfunction "2_2") (pintype "input"))
      (node (ref "X6") (pin "2") (pinfunction "TD-_2") (pintype "unspecified"))
    )
    (net (code "101") (name "unconnected-(DD1-CLK-Pad20)") (class "Default")
      (node (ref "DD1") (pin "20") (pinfunction "CLK_20") (pintype "unspecified"))
    )
    (net (code "102") (name "unconnected-(DD1-CMD-Pad19)") (class "Default")
      (node (ref "DD1") (pin "19") (pinfunction "CMD_19") (pintype "unspecified"))
    )
    (net (code "103") (name "unconnected-(DD1-NC-Pad32)") (class "Default")
      (node (ref "DD1") (pin "32") (pinfunction "NC_32") (pintype "unspecified"))
    )
    (net (code "104") (name "unconnected-(DD1-SD0-Pad21)") (class "Default")
      (node (ref "DD1") (pin "21") (pinfunction "SD0_21") (pintype "unspecified"))
    )
    (net (code "105") (name "unconnected-(DD1-SD1-Pad22)") (class "Default")
      (node (ref "DD1") (pin "22") (pinfunction "SD1_22") (pintype "unspecified"))
    )
    (net (code "106") (name "unconnected-(DD1-SD2-Pad17)") (class "Default")
      (node (ref "DD1") (pin "17") (pinfunction "SD2_17") (pintype "unspecified"))
    )
    (net (code "107") (name "unconnected-(DD1-SD3-Pad18)") (class "Default")
      (node (ref "DD1") (pin "18") (pinfunction "SD3_18") (pintype "unspecified"))
    )
    (net (code "108") (name "unconnected-(DD2-CTS#-Pad9)") (class "Default")
      (node (ref "DD2") (pin "9") (pinfunction "CTS#_9") (pintype "unspecified"))
    )
    (net (code "109") (name "unconnected-(DD2-DCD#-Pad12)") (class "Default")
      (node (ref "DD2") (pin "12") (pinfunction "DCD#_12") (pintype "unspecified"))
    )
    (net (code "110") (name "unconnected-(DD2-DSR#-Pad10)") (class "Default")
      (node (ref "DD2") (pin "10") (pinfunction "DSR#_10") (pintype "unspecified"))
    )
    (net (code "111") (name "unconnected-(DD2-R232-Pad15)") (class "Default")
      (node (ref "DD2") (pin "15") (pinfunction "R232_15") (pintype "unspecified"))
    )
    (net (code "112") (name "unconnected-(DD2-RI-Pad11)") (class "Default")
      (node (ref "DD2") (pin "11") (pinfunction "RI_11") (pintype "unspecified"))
    )
    (net (code "113") (name "unconnected-(DD4-NC-Pad5)") (class "Default")
      (node (ref "DD4") (pin "5") (pinfunction "NC_5") (pintype "unspecified"))
    )
    (net (code "114") (name "unconnected-(KEY1-Pad3)") (class "Default")
      (node (ref "KEY1") (pin "3") (pinfunction "3_3") (pintype "unspecified"))
    )
    (net (code "115") (name "unconnected-(KEY2-Pad3)") (class "Default")
      (node (ref "KEY2") (pin "3") (pinfunction "3_3") (pintype "unspecified"))
    )
    (net (code "116") (name "unconnected-(KEY3-Pad1)") (class "Default")
      (node (ref "KEY3") (pin "1") (pinfunction "1_1") (pintype "unspecified"))
    )
    (net (code "117") (name "unconnected-(KEY4-Pad4)") (class "Default")
      (node (ref "KEY4") (pin "4") (pinfunction "4_4") (pintype "unspecified"))
    )
    (net (code "118") (name "unconnected-(KEY6-Pad2)") (class "Default")
      (node (ref "KEY6") (pin "2") (pinfunction "2_2") (pintype "unspecified"))
    )
    (net (code "119") (name "unconnected-(KEY6-Pad4)") (class "Default")
      (node (ref "KEY6") (pin "4") (pinfunction "4_4") (pintype "unspecified"))
    )
    (net (code "120") (name "unconnected-(U1-A3-Pad4)") (class "Default")
      (node (ref "U1") (pin "4") (pinfunction "A3_4") (pintype "unspecified"))
    )
    (net (code "121") (name "unconnected-(U1-A4-Pad5)") (class "Default")
      (node (ref "U1") (pin "5") (pinfunction "A4_5") (pintype "unspecified"))
    )
    (net (code "122") (name "unconnected-(U1-A5-Pad6)") (class "Default")
      (node (ref "U1") (pin "6") (pinfunction "A5_6") (pintype "unspecified"))
    )
    (net (code "123") (name "unconnected-(U1-A6-Pad7)") (class "Default")
      (node (ref "U1") (pin "7") (pinfunction "A6_7") (pintype "unspecified"))
    )
    (net (code "124") (name "unconnected-(U1-A7-Pad8)") (class "Default")
      (node (ref "U1") (pin "8") (pinfunction "A7_8") (pintype "unspecified"))
    )
    (net (code "125") (name "unconnected-(U1-A8-Pad9)") (class "Default")
      (node (ref "U1") (pin "9") (pinfunction "A8_9") (pintype "unspecified"))
    )
    (net (code "126") (name "unconnected-(U1-B3-Pad17)") (class "Default")
      (node (ref "U1") (pin "17") (pinfunction "B3_17") (pintype "unspecified"))
    )
    (net (code "127") (name "unconnected-(U1-B4-Pad16)") (class "Default")
      (node (ref "U1") (pin "16") (pinfunction "B4_16") (pintype "unspecified"))
    )
    (net (code "128") (name "unconnected-(U1-B5-Pad15)") (class "Default")
      (node (ref "U1") (pin "15") (pinfunction "B5_15") (pintype "unspecified"))
    )
    (net (code "129") (name "unconnected-(U1-B6-Pad14)") (class "Default")
      (node (ref "U1") (pin "14") (pinfunction "B6_14") (pintype "unspecified"))
    )
    (net (code "130") (name "unconnected-(U1-B7-Pad13)") (class "Default")
      (node (ref "U1") (pin "13") (pinfunction "B7_13") (pintype "unspecified"))
    )
    (net (code "131") (name "unconnected-(U1-B8-Pad12)") (class "Default")
      (node (ref "U1") (pin "12") (pinfunction "B8_12") (pintype "unspecified"))
    )
    (net (code "132") (name "unconnected-(X2-ID-Pad4)") (class "Default")
      (node (ref "X2") (pin "4") (pinfunction "ID_4") (pintype "unspecified"))
    )
    (net (code "133") (name "unconnected-(X6-CHS_GND-Pad8)") (class "Default")
      (node (ref "X6") (pin "8") (pinfunction "CHS_GND_8") (pintype "unspecified"))
    )
    (net (code "134") (name "unconnected-(X6-NC-Pad7)") (class "Default")
      (node (ref "X6") (pin "7") (pinfunction "NC_7") (pintype "unspecified"))
    )
  )
)
